# Carte_Oeil.net
KiCad netlist of a schematic drawn in Altium Designer
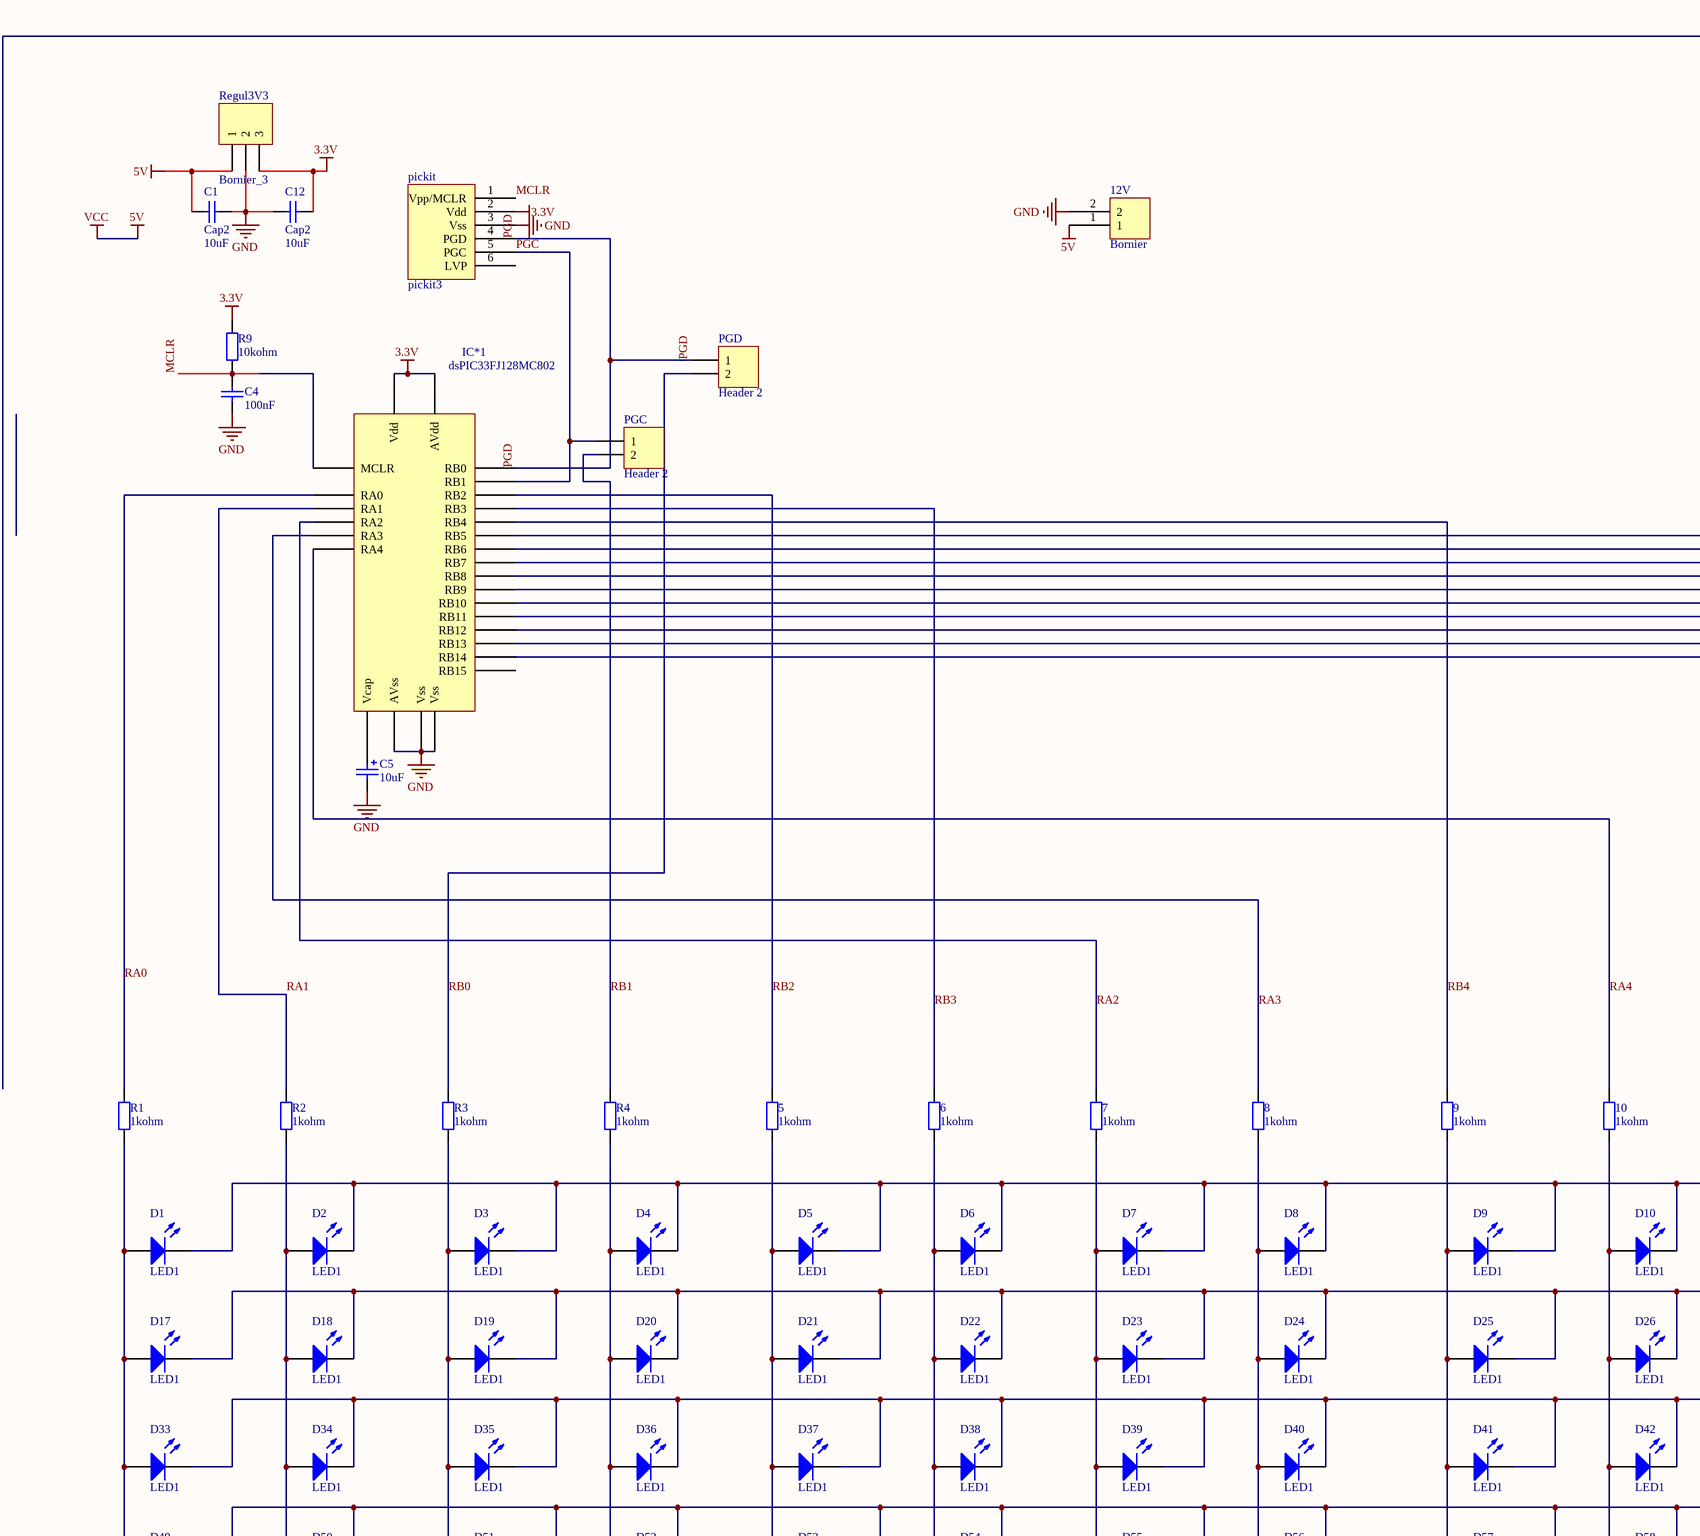
[diagram p0: Carte Oeil.SchDoc, top left]
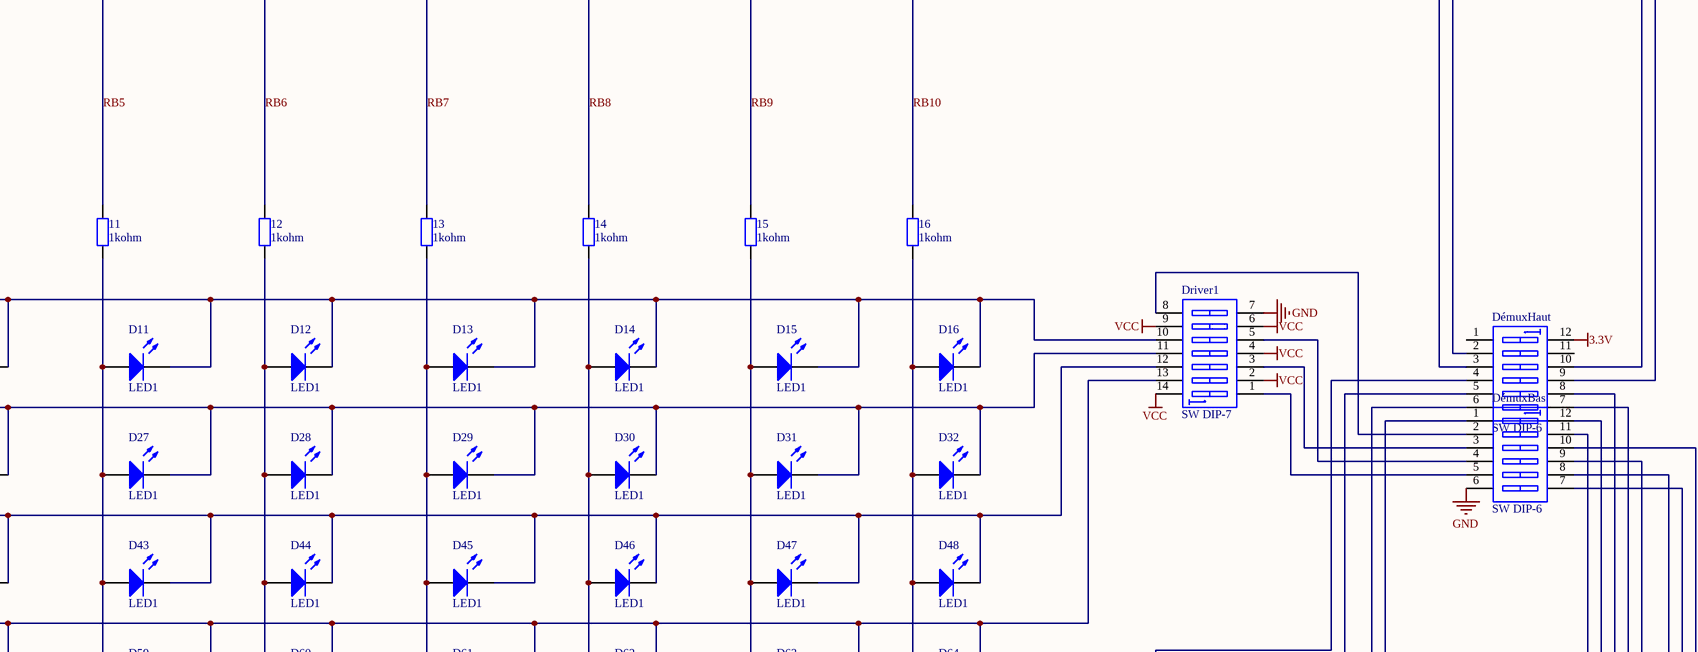
[diagram p1: Carte Oeil.SchDoc, top right]
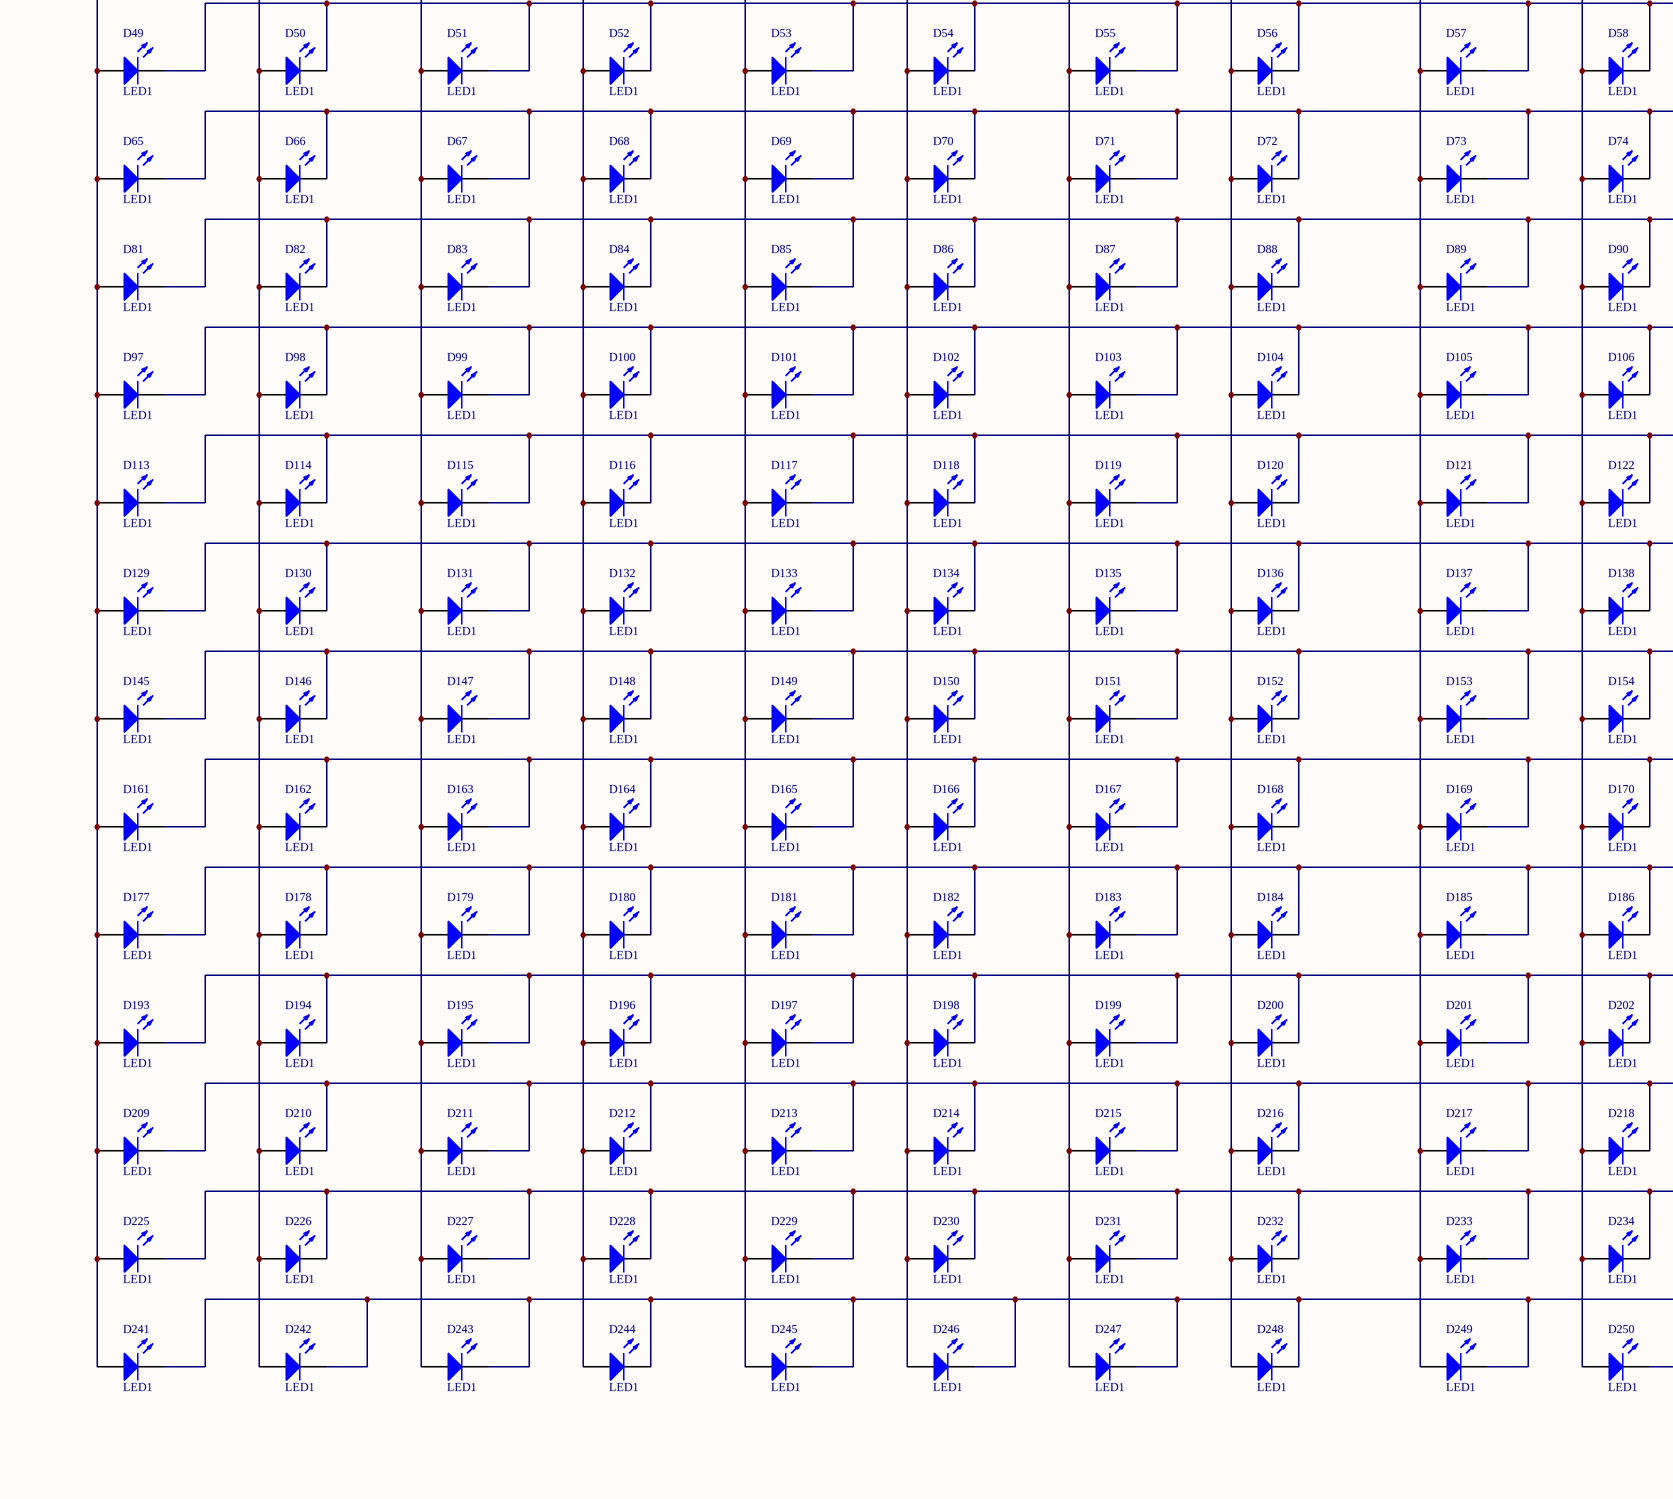
[diagram p2: Carte Oeil.SchDoc, bottom left]
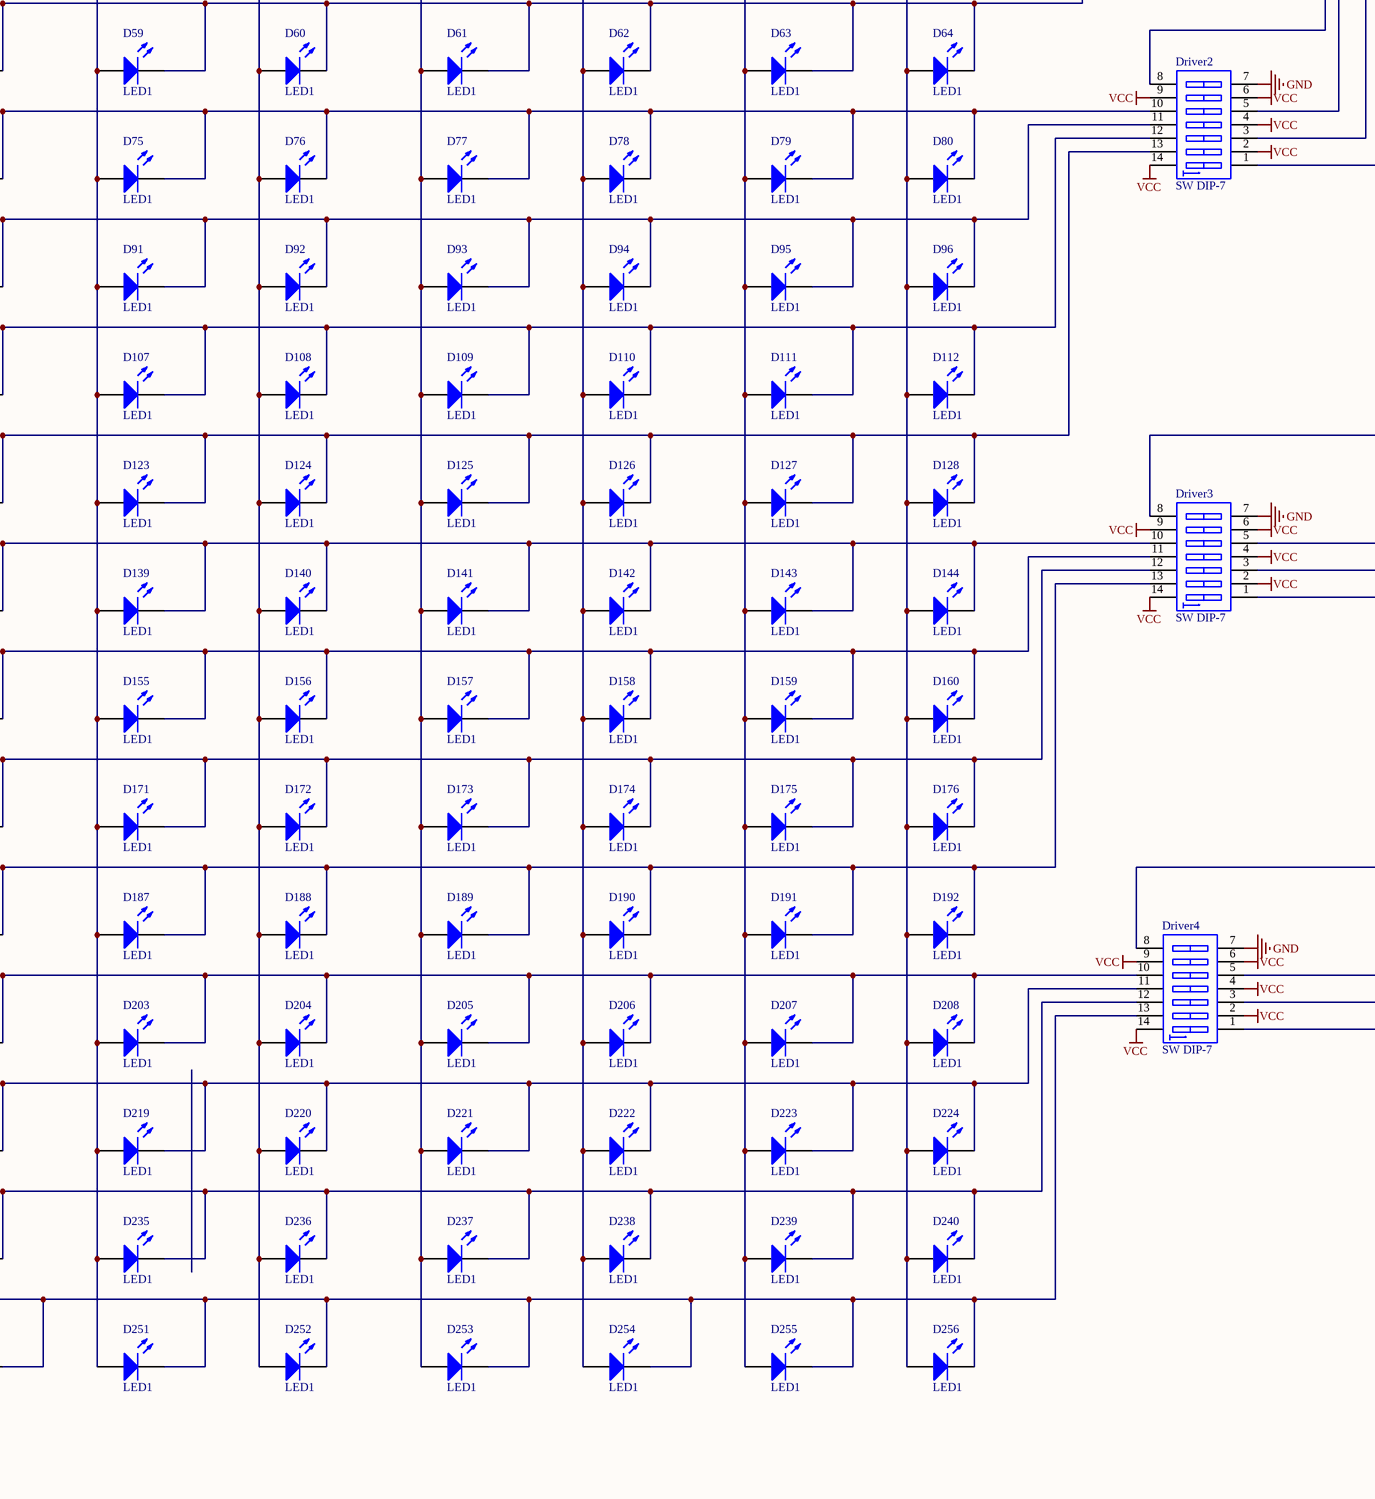
[diagram p3: Carte Oeil.SchDoc, bottom right]

(export (version "E")
  (design (tool "Eeschema 10.0.6"))
  (components
    (comp (ref "5")
      (value "1kohm")
      (footprint "AXIAL-0.5")
      (libsource (lib "lib_robotronik26092013") (part "Resistance"))
    )
    (comp (ref "6")
      (value "1kohm")
      (footprint "AXIAL-0.5")
      (libsource (lib "lib_robotronik26092013") (part "Resistance"))
    )
    (comp (ref "7")
      (value "1kohm")
      (footprint "AXIAL-0.5")
      (libsource (lib "lib_robotronik26092013") (part "Resistance"))
    )
    (comp (ref "8")
      (value "1kohm")
      (footprint "AXIAL-0.5")
      (libsource (lib "lib_robotronik26092013") (part "Resistance"))
    )
    (comp (ref "9")
      (value "1kohm")
      (footprint "AXIAL-0.5")
      (libsource (lib "lib_robotronik26092013") (part "Resistance"))
    )
    (comp (ref "10")
      (value "1kohm")
      (footprint "AXIAL-0.5")
      (libsource (lib "lib_robotronik26092013") (part "Resistance"))
    )
    (comp (ref "11")
      (value "1kohm")
      (footprint "AXIAL-0.5")
      (libsource (lib "lib_robotronik26092013") (part "Resistance"))
    )
    (comp (ref "12")
      (value "1kohm")
      (footprint "AXIAL-0.5")
      (libsource (lib "lib_robotronik26092013") (part "Resistance"))
    )
    (comp (ref "12V")
      (value "Bornier")
      (footprint "Bornier")
      (libsource (lib "lib_Robotronik") (part "Bornier2"))
    )
    (comp (ref "13")
      (value "1kohm")
      (footprint "AXIAL-0.5")
      (libsource (lib "lib_robotronik26092013") (part "Resistance"))
    )
    (comp (ref "14")
      (value "1kohm")
      (footprint "AXIAL-0.5")
      (libsource (lib "lib_robotronik26092013") (part "Resistance"))
    )
    (comp (ref "15")
      (value "1kohm")
      (footprint "AXIAL-0.5")
      (libsource (lib "lib_robotronik26092013") (part "Resistance"))
    )
    (comp (ref "16")
      (value "1kohm")
      (footprint "AXIAL-0.5")
      (libsource (lib "lib_robotronik26092013") (part "Resistance"))
    )
    (comp (ref "C1")
      (value "Cap2")
      (footprint "AXIAL-0.5")
      (description "Capacitor")
      (fields (field (name "ALTIUM_VALUE") "10uF") (field (name "PUBLISHER") "Altium Limited"))
      (libsource (lib "LIBRAIRIE_INTEGREE_PHELMA1") (part "Cap2"))
    )
    (comp (ref "C4") (value "100nF") (footprint "AXIAL-0.5") (libsource (lib "lib_Robotronik") (part "Capa")))
    (comp (ref "C5")
      (value "10uF")
      (footprint "AXIAL-0.5")
      (libsource (lib "lib_Robotronik") (part "Capa Pol"))
    )
    (comp (ref "C12")
      (value "Cap2")
      (footprint "AXIAL-0.5")
      (description "Capacitor")
      (fields (field (name "ALTIUM_VALUE") "10uF") (field (name "PUBLISHER") "Altium Limited"))
      (libsource (lib "LIBRAIRIE_INTEGREE_PHELMA1") (part "Cap2"))
    )
    (comp (ref "D1")
      (value "LED1")
      (footprint "LED-1")
      (description "Typical RED GaAs LED")
      (fields (field (name "PUBLISHER") "Altium Limited"))
      (libsource (lib "Miscellaneous Devices") (part "LED1"))
    )
    (comp (ref "D2")
      (value "LED1")
      (footprint "LED-1")
      (description "Typical RED GaAs LED")
      (fields (field (name "PUBLISHER") "Altium Limited"))
      (libsource (lib "Miscellaneous Devices") (part "LED1"))
    )
    (comp (ref "D3")
      (value "LED1")
      (footprint "LED-1")
      (description "Typical RED GaAs LED")
      (fields (field (name "PUBLISHER") "Altium Limited"))
      (libsource (lib "Miscellaneous Devices") (part "LED1"))
    )
    (comp (ref "D4")
      (value "LED1")
      (footprint "LED-1")
      (description "Typical RED GaAs LED")
      (fields (field (name "PUBLISHER") "Altium Limited"))
      (libsource (lib "Miscellaneous Devices") (part "LED1"))
    )
    (comp (ref "D5")
      (value "LED1")
      (footprint "LED-1")
      (description "Typical RED GaAs LED")
      (fields (field (name "PUBLISHER") "Altium Limited"))
      (libsource (lib "Miscellaneous Devices") (part "LED1"))
    )
    (comp (ref "D6")
      (value "LED1")
      (footprint "LED-1")
      (description "Typical RED GaAs LED")
      (fields (field (name "PUBLISHER") "Altium Limited"))
      (libsource (lib "Miscellaneous Devices") (part "LED1"))
    )
    (comp (ref "D7")
      (value "LED1")
      (footprint "LED-1")
      (description "Typical RED GaAs LED")
      (fields (field (name "PUBLISHER") "Altium Limited"))
      (libsource (lib "Miscellaneous Devices") (part "LED1"))
    )
    (comp (ref "D8")
      (value "LED1")
      (footprint "LED-1")
      (description "Typical RED GaAs LED")
      (fields (field (name "PUBLISHER") "Altium Limited"))
      (libsource (lib "Miscellaneous Devices") (part "LED1"))
    )
    (comp (ref "D9")
      (value "LED1")
      (footprint "LED-1")
      (description "Typical RED GaAs LED")
      (fields (field (name "PUBLISHER") "Altium Limited"))
      (libsource (lib "Miscellaneous Devices") (part "LED1"))
    )
    (comp (ref "D10")
      (value "LED1")
      (footprint "LED-1")
      (description "Typical RED GaAs LED")
      (fields (field (name "PUBLISHER") "Altium Limited"))
      (libsource (lib "Miscellaneous Devices") (part "LED1"))
    )
    (comp (ref "D11")
      (value "LED1")
      (footprint "LED-1")
      (description "Typical RED GaAs LED")
      (fields (field (name "PUBLISHER") "Altium Limited"))
      (libsource (lib "Miscellaneous Devices") (part "LED1"))
    )
    (comp (ref "D12")
      (value "LED1")
      (footprint "LED-1")
      (description "Typical RED GaAs LED")
      (fields (field (name "PUBLISHER") "Altium Limited"))
      (libsource (lib "Miscellaneous Devices") (part "LED1"))
    )
    (comp (ref "D13")
      (value "LED1")
      (footprint "LED-1")
      (description "Typical RED GaAs LED")
      (fields (field (name "PUBLISHER") "Altium Limited"))
      (libsource (lib "Miscellaneous Devices") (part "LED1"))
    )
    (comp (ref "D14")
      (value "LED1")
      (footprint "LED-1")
      (description "Typical RED GaAs LED")
      (fields (field (name "PUBLISHER") "Altium Limited"))
      (libsource (lib "Miscellaneous Devices") (part "LED1"))
    )
    (comp (ref "D15")
      (value "LED1")
      (footprint "LED-1")
      (description "Typical RED GaAs LED")
      (fields (field (name "PUBLISHER") "Altium Limited"))
      (libsource (lib "Miscellaneous Devices") (part "LED1"))
    )
    (comp (ref "D16")
      (value "LED1")
      (footprint "LED-1")
      (description "Typical RED GaAs LED")
      (fields (field (name "PUBLISHER") "Altium Limited"))
      (libsource (lib "Miscellaneous Devices") (part "LED1"))
    )
    (comp (ref "D17")
      (value "LED1")
      (footprint "LED-1")
      (description "Typical RED GaAs LED")
      (fields (field (name "PUBLISHER") "Altium Limited"))
      (libsource (lib "Miscellaneous Devices") (part "LED1"))
    )
    (comp (ref "D18")
      (value "LED1")
      (footprint "LED-1")
      (description "Typical RED GaAs LED")
      (fields (field (name "PUBLISHER") "Altium Limited"))
      (libsource (lib "Miscellaneous Devices") (part "LED1"))
    )
    (comp (ref "D19")
      (value "LED1")
      (footprint "LED-1")
      (description "Typical RED GaAs LED")
      (fields (field (name "PUBLISHER") "Altium Limited"))
      (libsource (lib "Miscellaneous Devices") (part "LED1"))
    )
    (comp (ref "D20")
      (value "LED1")
      (footprint "LED-1")
      (description "Typical RED GaAs LED")
      (fields (field (name "PUBLISHER") "Altium Limited"))
      (libsource (lib "Miscellaneous Devices") (part "LED1"))
    )
    (comp (ref "D21")
      (value "LED1")
      (footprint "LED-1")
      (description "Typical RED GaAs LED")
      (fields (field (name "PUBLISHER") "Altium Limited"))
      (libsource (lib "Miscellaneous Devices") (part "LED1"))
    )
    (comp (ref "D22")
      (value "LED1")
      (footprint "LED-1")
      (description "Typical RED GaAs LED")
      (fields (field (name "PUBLISHER") "Altium Limited"))
      (libsource (lib "Miscellaneous Devices") (part "LED1"))
    )
    (comp (ref "D23")
      (value "LED1")
      (footprint "LED-1")
      (description "Typical RED GaAs LED")
      (fields (field (name "PUBLISHER") "Altium Limited"))
      (libsource (lib "Miscellaneous Devices") (part "LED1"))
    )
    (comp (ref "D24")
      (value "LED1")
      (footprint "LED-1")
      (description "Typical RED GaAs LED")
      (fields (field (name "PUBLISHER") "Altium Limited"))
      (libsource (lib "Miscellaneous Devices") (part "LED1"))
    )
    (comp (ref "D25")
      (value "LED1")
      (footprint "LED-1")
      (description "Typical RED GaAs LED")
      (fields (field (name "PUBLISHER") "Altium Limited"))
      (libsource (lib "Miscellaneous Devices") (part "LED1"))
    )
    (comp (ref "D26")
      (value "LED1")
      (footprint "LED-1")
      (description "Typical RED GaAs LED")
      (fields (field (name "PUBLISHER") "Altium Limited"))
      (libsource (lib "Miscellaneous Devices") (part "LED1"))
    )
    (comp (ref "D27")
      (value "LED1")
      (footprint "LED-1")
      (description "Typical RED GaAs LED")
      (fields (field (name "PUBLISHER") "Altium Limited"))
      (libsource (lib "Miscellaneous Devices") (part "LED1"))
    )
    (comp (ref "D28")
      (value "LED1")
      (footprint "LED-1")
      (description "Typical RED GaAs LED")
      (fields (field (name "PUBLISHER") "Altium Limited"))
      (libsource (lib "Miscellaneous Devices") (part "LED1"))
    )
    (comp (ref "D29")
      (value "LED1")
      (footprint "LED-1")
      (description "Typical RED GaAs LED")
      (fields (field (name "PUBLISHER") "Altium Limited"))
      (libsource (lib "Miscellaneous Devices") (part "LED1"))
    )
    (comp (ref "D30")
      (value "LED1")
      (footprint "LED-1")
      (description "Typical RED GaAs LED")
      (fields (field (name "PUBLISHER") "Altium Limited"))
      (libsource (lib "Miscellaneous Devices") (part "LED1"))
    )
    (comp (ref "D31")
      (value "LED1")
      (footprint "LED-1")
      (description "Typical RED GaAs LED")
      (fields (field (name "PUBLISHER") "Altium Limited"))
      (libsource (lib "Miscellaneous Devices") (part "LED1"))
    )
    (comp (ref "D32")
      (value "LED1")
      (footprint "LED-1")
      (description "Typical RED GaAs LED")
      (fields (field (name "PUBLISHER") "Altium Limited"))
      (libsource (lib "Miscellaneous Devices") (part "LED1"))
    )
    (comp (ref "D33")
      (value "LED1")
      (footprint "LED-1")
      (description "Typical RED GaAs LED")
      (fields (field (name "PUBLISHER") "Altium Limited"))
      (libsource (lib "Miscellaneous Devices") (part "LED1"))
    )
    (comp (ref "D34")
      (value "LED1")
      (footprint "LED-1")
      (description "Typical RED GaAs LED")
      (fields (field (name "PUBLISHER") "Altium Limited"))
      (libsource (lib "Miscellaneous Devices") (part "LED1"))
    )
    (comp (ref "D35")
      (value "LED1")
      (footprint "LED-1")
      (description "Typical RED GaAs LED")
      (fields (field (name "PUBLISHER") "Altium Limited"))
      (libsource (lib "Miscellaneous Devices") (part "LED1"))
    )
    (comp (ref "D36")
      (value "LED1")
      (footprint "LED-1")
      (description "Typical RED GaAs LED")
      (fields (field (name "PUBLISHER") "Altium Limited"))
      (libsource (lib "Miscellaneous Devices") (part "LED1"))
    )
    (comp (ref "D37")
      (value "LED1")
      (footprint "LED-1")
      (description "Typical RED GaAs LED")
      (fields (field (name "PUBLISHER") "Altium Limited"))
      (libsource (lib "Miscellaneous Devices") (part "LED1"))
    )
    (comp (ref "D38")
      (value "LED1")
      (footprint "LED-1")
      (description "Typical RED GaAs LED")
      (fields (field (name "PUBLISHER") "Altium Limited"))
      (libsource (lib "Miscellaneous Devices") (part "LED1"))
    )
    (comp (ref "D39")
      (value "LED1")
      (footprint "LED-1")
      (description "Typical RED GaAs LED")
      (fields (field (name "PUBLISHER") "Altium Limited"))
      (libsource (lib "Miscellaneous Devices") (part "LED1"))
    )
    (comp (ref "D40")
      (value "LED1")
      (footprint "LED-1")
      (description "Typical RED GaAs LED")
      (fields (field (name "PUBLISHER") "Altium Limited"))
      (libsource (lib "Miscellaneous Devices") (part "LED1"))
    )
    (comp (ref "D41")
      (value "LED1")
      (footprint "LED-1")
      (description "Typical RED GaAs LED")
      (fields (field (name "PUBLISHER") "Altium Limited"))
      (libsource (lib "Miscellaneous Devices") (part "LED1"))
    )
    (comp (ref "D42")
      (value "LED1")
      (footprint "LED-1")
      (description "Typical RED GaAs LED")
      (fields (field (name "PUBLISHER") "Altium Limited"))
      (libsource (lib "Miscellaneous Devices") (part "LED1"))
    )
    (comp (ref "D43")
      (value "LED1")
      (footprint "LED-1")
      (description "Typical RED GaAs LED")
      (fields (field (name "PUBLISHER") "Altium Limited"))
      (libsource (lib "Miscellaneous Devices") (part "LED1"))
    )
    (comp (ref "D44")
      (value "LED1")
      (footprint "LED-1")
      (description "Typical RED GaAs LED")
      (fields (field (name "PUBLISHER") "Altium Limited"))
      (libsource (lib "Miscellaneous Devices") (part "LED1"))
    )
    (comp (ref "D45")
      (value "LED1")
      (footprint "LED-1")
      (description "Typical RED GaAs LED")
      (fields (field (name "PUBLISHER") "Altium Limited"))
      (libsource (lib "Miscellaneous Devices") (part "LED1"))
    )
    (comp (ref "D46")
      (value "LED1")
      (footprint "LED-1")
      (description "Typical RED GaAs LED")
      (fields (field (name "PUBLISHER") "Altium Limited"))
      (libsource (lib "Miscellaneous Devices") (part "LED1"))
    )
    (comp (ref "D47")
      (value "LED1")
      (footprint "LED-1")
      (description "Typical RED GaAs LED")
      (fields (field (name "PUBLISHER") "Altium Limited"))
      (libsource (lib "Miscellaneous Devices") (part "LED1"))
    )
    (comp (ref "D48")
      (value "LED1")
      (footprint "LED-1")
      (description "Typical RED GaAs LED")
      (fields (field (name "PUBLISHER") "Altium Limited"))
      (libsource (lib "Miscellaneous Devices") (part "LED1"))
    )
    (comp (ref "D49")
      (value "LED1")
      (footprint "LED-1")
      (description "Typical RED GaAs LED")
      (fields (field (name "PUBLISHER") "Altium Limited"))
      (libsource (lib "Miscellaneous Devices") (part "LED1"))
    )
    (comp (ref "D50")
      (value "LED1")
      (footprint "LED-1")
      (description "Typical RED GaAs LED")
      (fields (field (name "PUBLISHER") "Altium Limited"))
      (libsource (lib "Miscellaneous Devices") (part "LED1"))
    )
    (comp (ref "D51")
      (value "LED1")
      (footprint "LED-1")
      (description "Typical RED GaAs LED")
      (fields (field (name "PUBLISHER") "Altium Limited"))
      (libsource (lib "Miscellaneous Devices") (part "LED1"))
    )
    (comp (ref "D52")
      (value "LED1")
      (footprint "LED-1")
      (description "Typical RED GaAs LED")
      (fields (field (name "PUBLISHER") "Altium Limited"))
      (libsource (lib "Miscellaneous Devices") (part "LED1"))
    )
    (comp (ref "D53")
      (value "LED1")
      (footprint "LED-1")
      (description "Typical RED GaAs LED")
      (fields (field (name "PUBLISHER") "Altium Limited"))
      (libsource (lib "Miscellaneous Devices") (part "LED1"))
    )
    (comp (ref "D54")
      (value "LED1")
      (footprint "LED-1")
      (description "Typical RED GaAs LED")
      (fields (field (name "PUBLISHER") "Altium Limited"))
      (libsource (lib "Miscellaneous Devices") (part "LED1"))
    )
    (comp (ref "D55")
      (value "LED1")
      (footprint "LED-1")
      (description "Typical RED GaAs LED")
      (fields (field (name "PUBLISHER") "Altium Limited"))
      (libsource (lib "Miscellaneous Devices") (part "LED1"))
    )
    (comp (ref "D56")
      (value "LED1")
      (footprint "LED-1")
      (description "Typical RED GaAs LED")
      (fields (field (name "PUBLISHER") "Altium Limited"))
      (libsource (lib "Miscellaneous Devices") (part "LED1"))
    )
    (comp (ref "D57")
      (value "LED1")
      (footprint "LED-1")
      (description "Typical RED GaAs LED")
      (fields (field (name "PUBLISHER") "Altium Limited"))
      (libsource (lib "Miscellaneous Devices") (part "LED1"))
    )
    (comp (ref "D58")
      (value "LED1")
      (footprint "LED-1")
      (description "Typical RED GaAs LED")
      (fields (field (name "PUBLISHER") "Altium Limited"))
      (libsource (lib "Miscellaneous Devices") (part "LED1"))
    )
    (comp (ref "D59")
      (value "LED1")
      (footprint "LED-1")
      (description "Typical RED GaAs LED")
      (fields (field (name "PUBLISHER") "Altium Limited"))
      (libsource (lib "Miscellaneous Devices") (part "LED1"))
    )
    (comp (ref "D60")
      (value "LED1")
      (footprint "LED-1")
      (description "Typical RED GaAs LED")
      (fields (field (name "PUBLISHER") "Altium Limited"))
      (libsource (lib "Miscellaneous Devices") (part "LED1"))
    )
    (comp (ref "D61")
      (value "LED1")
      (footprint "LED-1")
      (description "Typical RED GaAs LED")
      (fields (field (name "PUBLISHER") "Altium Limited"))
      (libsource (lib "Miscellaneous Devices") (part "LED1"))
    )
    (comp (ref "D62")
      (value "LED1")
      (footprint "LED-1")
      (description "Typical RED GaAs LED")
      (fields (field (name "PUBLISHER") "Altium Limited"))
      (libsource (lib "Miscellaneous Devices") (part "LED1"))
    )
    (comp (ref "D63")
      (value "LED1")
      (footprint "LED-1")
      (description "Typical RED GaAs LED")
      (fields (field (name "PUBLISHER") "Altium Limited"))
      (libsource (lib "Miscellaneous Devices") (part "LED1"))
    )
    (comp (ref "D64")
      (value "LED1")
      (footprint "LED-1")
      (description "Typical RED GaAs LED")
      (fields (field (name "PUBLISHER") "Altium Limited"))
      (libsource (lib "Miscellaneous Devices") (part "LED1"))
    )
    (comp (ref "D65")
      (value "LED1")
      (footprint "LED-1")
      (description "Typical RED GaAs LED")
      (fields (field (name "PUBLISHER") "Altium Limited"))
      (libsource (lib "Miscellaneous Devices") (part "LED1"))
    )
    (comp (ref "D66")
      (value "LED1")
      (footprint "LED-1")
      (description "Typical RED GaAs LED")
      (fields (field (name "PUBLISHER") "Altium Limited"))
      (libsource (lib "Miscellaneous Devices") (part "LED1"))
    )
    (comp (ref "D67")
      (value "LED1")
      (footprint "LED-1")
      (description "Typical RED GaAs LED")
      (fields (field (name "PUBLISHER") "Altium Limited"))
      (libsource (lib "Miscellaneous Devices") (part "LED1"))
    )
    (comp (ref "D68")
      (value "LED1")
      (footprint "LED-1")
      (description "Typical RED GaAs LED")
      (fields (field (name "PUBLISHER") "Altium Limited"))
      (libsource (lib "Miscellaneous Devices") (part "LED1"))
    )
    (comp (ref "D69")
      (value "LED1")
      (footprint "LED-1")
      (description "Typical RED GaAs LED")
      (fields (field (name "PUBLISHER") "Altium Limited"))
      (libsource (lib "Miscellaneous Devices") (part "LED1"))
    )
    (comp (ref "D70")
      (value "LED1")
      (footprint "LED-1")
      (description "Typical RED GaAs LED")
      (fields (field (name "PUBLISHER") "Altium Limited"))
      (libsource (lib "Miscellaneous Devices") (part "LED1"))
    )
    (comp (ref "D71")
      (value "LED1")
      (footprint "LED-1")
      (description "Typical RED GaAs LED")
      (fields (field (name "PUBLISHER") "Altium Limited"))
      (libsource (lib "Miscellaneous Devices") (part "LED1"))
    )
    (comp (ref "D72")
      (value "LED1")
      (footprint "LED-1")
      (description "Typical RED GaAs LED")
      (fields (field (name "PUBLISHER") "Altium Limited"))
      (libsource (lib "Miscellaneous Devices") (part "LED1"))
    )
    (comp (ref "D73")
      (value "LED1")
      (footprint "LED-1")
      (description "Typical RED GaAs LED")
      (fields (field (name "PUBLISHER") "Altium Limited"))
      (libsource (lib "Miscellaneous Devices") (part "LED1"))
    )
    (comp (ref "D74")
      (value "LED1")
      (footprint "LED-1")
      (description "Typical RED GaAs LED")
      (fields (field (name "PUBLISHER") "Altium Limited"))
      (libsource (lib "Miscellaneous Devices") (part "LED1"))
    )
    (comp (ref "D75")
      (value "LED1")
      (footprint "LED-1")
      (description "Typical RED GaAs LED")
      (fields (field (name "PUBLISHER") "Altium Limited"))
      (libsource (lib "Miscellaneous Devices") (part "LED1"))
    )
    (comp (ref "D76")
      (value "LED1")
      (footprint "LED-1")
      (description "Typical RED GaAs LED")
      (fields (field (name "PUBLISHER") "Altium Limited"))
      (libsource (lib "Miscellaneous Devices") (part "LED1"))
    )
    (comp (ref "D77")
      (value "LED1")
      (footprint "LED-1")
      (description "Typical RED GaAs LED")
      (fields (field (name "PUBLISHER") "Altium Limited"))
      (libsource (lib "Miscellaneous Devices") (part "LED1"))
    )
    (comp (ref "D78")
      (value "LED1")
      (footprint "LED-1")
      (description "Typical RED GaAs LED")
      (fields (field (name "PUBLISHER") "Altium Limited"))
      (libsource (lib "Miscellaneous Devices") (part "LED1"))
    )
    (comp (ref "D79")
      (value "LED1")
      (footprint "LED-1")
      (description "Typical RED GaAs LED")
      (fields (field (name "PUBLISHER") "Altium Limited"))
      (libsource (lib "Miscellaneous Devices") (part "LED1"))
    )
    (comp (ref "D80")
      (value "LED1")
      (footprint "LED-1")
      (description "Typical RED GaAs LED")
      (fields (field (name "PUBLISHER") "Altium Limited"))
      (libsource (lib "Miscellaneous Devices") (part "LED1"))
    )
    (comp (ref "D81")
      (value "LED1")
      (footprint "LED-1")
      (description "Typical RED GaAs LED")
      (fields (field (name "PUBLISHER") "Altium Limited"))
      (libsource (lib "Miscellaneous Devices") (part "LED1"))
    )
    (comp (ref "D82")
      (value "LED1")
      (footprint "LED-1")
      (description "Typical RED GaAs LED")
      (fields (field (name "PUBLISHER") "Altium Limited"))
      (libsource (lib "Miscellaneous Devices") (part "LED1"))
    )
    (comp (ref "D83")
      (value "LED1")
      (footprint "LED-1")
      (description "Typical RED GaAs LED")
      (fields (field (name "PUBLISHER") "Altium Limited"))
      (libsource (lib "Miscellaneous Devices") (part "LED1"))
    )
    (comp (ref "D84")
      (value "LED1")
      (footprint "LED-1")
      (description "Typical RED GaAs LED")
      (fields (field (name "PUBLISHER") "Altium Limited"))
      (libsource (lib "Miscellaneous Devices") (part "LED1"))
    )
    (comp (ref "D85")
      (value "LED1")
      (footprint "LED-1")
      (description "Typical RED GaAs LED")
      (fields (field (name "PUBLISHER") "Altium Limited"))
      (libsource (lib "Miscellaneous Devices") (part "LED1"))
    )
    (comp (ref "D86")
      (value "LED1")
      (footprint "LED-1")
      (description "Typical RED GaAs LED")
      (fields (field (name "PUBLISHER") "Altium Limited"))
      (libsource (lib "Miscellaneous Devices") (part "LED1"))
    )
    (comp (ref "D87")
      (value "LED1")
      (footprint "LED-1")
      (description "Typical RED GaAs LED")
      (fields (field (name "PUBLISHER") "Altium Limited"))
      (libsource (lib "Miscellaneous Devices") (part "LED1"))
    )
    (comp (ref "D88")
      (value "LED1")
      (footprint "LED-1")
      (description "Typical RED GaAs LED")
      (fields (field (name "PUBLISHER") "Altium Limited"))
      (libsource (lib "Miscellaneous Devices") (part "LED1"))
    )
    (comp (ref "D89")
      (value "LED1")
      (footprint "LED-1")
      (description "Typical RED GaAs LED")
      (fields (field (name "PUBLISHER") "Altium Limited"))
      (libsource (lib "Miscellaneous Devices") (part "LED1"))
    )
    (comp (ref "D90")
      (value "LED1")
      (footprint "LED-1")
      (description "Typical RED GaAs LED")
      (fields (field (name "PUBLISHER") "Altium Limited"))
      (libsource (lib "Miscellaneous Devices") (part "LED1"))
    )
    (comp (ref "D91")
      (value "LED1")
      (footprint "LED-1")
      (description "Typical RED GaAs LED")
      (fields (field (name "PUBLISHER") "Altium Limited"))
      (libsource (lib "Miscellaneous Devices") (part "LED1"))
    )
    (comp (ref "D92")
      (value "LED1")
      (footprint "LED-1")
      (description "Typical RED GaAs LED")
      (fields (field (name "PUBLISHER") "Altium Limited"))
      (libsource (lib "Miscellaneous Devices") (part "LED1"))
    )
    (comp (ref "D93")
      (value "LED1")
      (footprint "LED-1")
      (description "Typical RED GaAs LED")
      (fields (field (name "PUBLISHER") "Altium Limited"))
      (libsource (lib "Miscellaneous Devices") (part "LED1"))
    )
    (comp (ref "D94")
      (value "LED1")
      (footprint "LED-1")
      (description "Typical RED GaAs LED")
      (fields (field (name "PUBLISHER") "Altium Limited"))
      (libsource (lib "Miscellaneous Devices") (part "LED1"))
    )
    (comp (ref "D95")
      (value "LED1")
      (footprint "LED-1")
      (description "Typical RED GaAs LED")
      (fields (field (name "PUBLISHER") "Altium Limited"))
      (libsource (lib "Miscellaneous Devices") (part "LED1"))
    )
    (comp (ref "D96")
      (value "LED1")
      (footprint "LED-1")
      (description "Typical RED GaAs LED")
      (fields (field (name "PUBLISHER") "Altium Limited"))
      (libsource (lib "Miscellaneous Devices") (part "LED1"))
    )
    (comp (ref "D97")
      (value "LED1")
      (footprint "LED-1")
      (description "Typical RED GaAs LED")
      (fields (field (name "PUBLISHER") "Altium Limited"))
      (libsource (lib "Miscellaneous Devices") (part "LED1"))
    )
    (comp (ref "D98")
      (value "LED1")
      (footprint "LED-1")
      (description "Typical RED GaAs LED")
      (fields (field (name "PUBLISHER") "Altium Limited"))
      (libsource (lib "Miscellaneous Devices") (part "LED1"))
    )
    (comp (ref "D99")
      (value "LED1")
      (footprint "LED-1")
      (description "Typical RED GaAs LED")
      (fields (field (name "PUBLISHER") "Altium Limited"))
      (libsource (lib "Miscellaneous Devices") (part "LED1"))
    )
    (comp (ref "D100")
      (value "LED1")
      (footprint "LED-1")
      (description "Typical RED GaAs LED")
      (fields (field (name "PUBLISHER") "Altium Limited"))
      (libsource (lib "Miscellaneous Devices") (part "LED1"))
    )
    (comp (ref "D101")
      (value "LED1")
      (footprint "LED-1")
      (description "Typical RED GaAs LED")
      (fields (field (name "PUBLISHER") "Altium Limited"))
      (libsource (lib "Miscellaneous Devices") (part "LED1"))
    )
    (comp (ref "D102")
      (value "LED1")
      (footprint "LED-1")
      (description "Typical RED GaAs LED")
      (fields (field (name "PUBLISHER") "Altium Limited"))
      (libsource (lib "Miscellaneous Devices") (part "LED1"))
    )
    (comp (ref "D103")
      (value "LED1")
      (footprint "LED-1")
      (description "Typical RED GaAs LED")
      (fields (field (name "PUBLISHER") "Altium Limited"))
      (libsource (lib "Miscellaneous Devices") (part "LED1"))
    )
    (comp (ref "D104")
      (value "LED1")
      (footprint "LED-1")
      (description "Typical RED GaAs LED")
      (fields (field (name "PUBLISHER") "Altium Limited"))
      (libsource (lib "Miscellaneous Devices") (part "LED1"))
    )
    (comp (ref "D105")
      (value "LED1")
      (footprint "LED-1")
      (description "Typical RED GaAs LED")
      (fields (field (name "PUBLISHER") "Altium Limited"))
      (libsource (lib "Miscellaneous Devices") (part "LED1"))
    )
    (comp (ref "D106")
      (value "LED1")
      (footprint "LED-1")
      (description "Typical RED GaAs LED")
      (fields (field (name "PUBLISHER") "Altium Limited"))
      (libsource (lib "Miscellaneous Devices") (part "LED1"))
    )
    (comp (ref "D107")
      (value "LED1")
      (footprint "LED-1")
      (description "Typical RED GaAs LED")
      (fields (field (name "PUBLISHER") "Altium Limited"))
      (libsource (lib "Miscellaneous Devices") (part "LED1"))
    )
    (comp (ref "D108")
      (value "LED1")
      (footprint "LED-1")
      (description "Typical RED GaAs LED")
      (fields (field (name "PUBLISHER") "Altium Limited"))
      (libsource (lib "Miscellaneous Devices") (part "LED1"))
    )
    (comp (ref "D109")
      (value "LED1")
      (footprint "LED-1")
      (description "Typical RED GaAs LED")
      (fields (field (name "PUBLISHER") "Altium Limited"))
      (libsource (lib "Miscellaneous Devices") (part "LED1"))
    )
    (comp (ref "D110")
      (value "LED1")
      (footprint "LED-1")
      (description "Typical RED GaAs LED")
      (fields (field (name "PUBLISHER") "Altium Limited"))
      (libsource (lib "Miscellaneous Devices") (part "LED1"))
    )
    (comp (ref "D111")
      (value "LED1")
      (footprint "LED-1")
      (description "Typical RED GaAs LED")
      (fields (field (name "PUBLISHER") "Altium Limited"))
      (libsource (lib "Miscellaneous Devices") (part "LED1"))
    )
    (comp (ref "D112")
      (value "LED1")
      (footprint "LED-1")
      (description "Typical RED GaAs LED")
      (fields (field (name "PUBLISHER") "Altium Limited"))
      (libsource (lib "Miscellaneous Devices") (part "LED1"))
    )
    (comp (ref "D113")
      (value "LED1")
      (footprint "LED-1")
      (description "Typical RED GaAs LED")
      (fields (field (name "PUBLISHER") "Altium Limited"))
      (libsource (lib "Miscellaneous Devices") (part "LED1"))
    )
    (comp (ref "D114")
      (value "LED1")
      (footprint "LED-1")
      (description "Typical RED GaAs LED")
      (fields (field (name "PUBLISHER") "Altium Limited"))
      (libsource (lib "Miscellaneous Devices") (part "LED1"))
    )
    (comp (ref "D115")
      (value "LED1")
      (footprint "LED-1")
      (description "Typical RED GaAs LED")
      (fields (field (name "PUBLISHER") "Altium Limited"))
      (libsource (lib "Miscellaneous Devices") (part "LED1"))
    )
    (comp (ref "D116")
      (value "LED1")
      (footprint "LED-1")
      (description "Typical RED GaAs LED")
      (fields (field (name "PUBLISHER") "Altium Limited"))
      (libsource (lib "Miscellaneous Devices") (part "LED1"))
    )
    (comp (ref "D117")
      (value "LED1")
      (footprint "LED-1")
      (description "Typical RED GaAs LED")
      (fields (field (name "PUBLISHER") "Altium Limited"))
      (libsource (lib "Miscellaneous Devices") (part "LED1"))
    )
    (comp (ref "D118")
      (value "LED1")
      (footprint "LED-1")
      (description "Typical RED GaAs LED")
      (fields (field (name "PUBLISHER") "Altium Limited"))
      (libsource (lib "Miscellaneous Devices") (part "LED1"))
    )
    (comp (ref "D119")
      (value "LED1")
      (footprint "LED-1")
      (description "Typical RED GaAs LED")
      (fields (field (name "PUBLISHER") "Altium Limited"))
      (libsource (lib "Miscellaneous Devices") (part "LED1"))
    )
    (comp (ref "D120")
      (value "LED1")
      (footprint "LED-1")
      (description "Typical RED GaAs LED")
      (fields (field (name "PUBLISHER") "Altium Limited"))
      (libsource (lib "Miscellaneous Devices") (part "LED1"))
    )
    (comp (ref "D121")
      (value "LED1")
      (footprint "LED-1")
      (description "Typical RED GaAs LED")
      (fields (field (name "PUBLISHER") "Altium Limited"))
      (libsource (lib "Miscellaneous Devices") (part "LED1"))
    )
    (comp (ref "D122")
      (value "LED1")
      (footprint "LED-1")
      (description "Typical RED GaAs LED")
      (fields (field (name "PUBLISHER") "Altium Limited"))
      (libsource (lib "Miscellaneous Devices") (part "LED1"))
    )
    (comp (ref "D123")
      (value "LED1")
      (footprint "LED-1")
      (description "Typical RED GaAs LED")
      (fields (field (name "PUBLISHER") "Altium Limited"))
      (libsource (lib "Miscellaneous Devices") (part "LED1"))
    )
    (comp (ref "D124")
      (value "LED1")
      (footprint "LED-1")
      (description "Typical RED GaAs LED")
      (fields (field (name "PUBLISHER") "Altium Limited"))
      (libsource (lib "Miscellaneous Devices") (part "LED1"))
    )
    (comp (ref "D125")
      (value "LED1")
      (footprint "LED-1")
      (description "Typical RED GaAs LED")
      (fields (field (name "PUBLISHER") "Altium Limited"))
      (libsource (lib "Miscellaneous Devices") (part "LED1"))
    )
    (comp (ref "D126")
      (value "LED1")
      (footprint "LED-1")
      (description "Typical RED GaAs LED")
      (fields (field (name "PUBLISHER") "Altium Limited"))
      (libsource (lib "Miscellaneous Devices") (part "LED1"))
    )
    (comp (ref "D127")
      (value "LED1")
      (footprint "LED-1")
      (description "Typical RED GaAs LED")
      (fields (field (name "PUBLISHER") "Altium Limited"))
      (libsource (lib "Miscellaneous Devices") (part "LED1"))
    )
    (comp (ref "D128")
      (value "LED1")
      (footprint "LED-1")
      (description "Typical RED GaAs LED")
      (fields (field (name "PUBLISHER") "Altium Limited"))
      (libsource (lib "Miscellaneous Devices") (part "LED1"))
    )
    (comp (ref "D129")
      (value "LED1")
      (footprint "LED-1")
      (description "Typical RED GaAs LED")
      (fields (field (name "PUBLISHER") "Altium Limited"))
      (libsource (lib "Miscellaneous Devices") (part "LED1"))
    )
    (comp (ref "D130")
      (value "LED1")
      (footprint "LED-1")
      (description "Typical RED GaAs LED")
      (fields (field (name "PUBLISHER") "Altium Limited"))
      (libsource (lib "Miscellaneous Devices") (part "LED1"))
    )
    (comp (ref "D131")
      (value "LED1")
      (footprint "LED-1")
      (description "Typical RED GaAs LED")
      (fields (field (name "PUBLISHER") "Altium Limited"))
      (libsource (lib "Miscellaneous Devices") (part "LED1"))
    )
    (comp (ref "D132")
      (value "LED1")
      (footprint "LED-1")
      (description "Typical RED GaAs LED")
      (fields (field (name "PUBLISHER") "Altium Limited"))
      (libsource (lib "Miscellaneous Devices") (part "LED1"))
    )
    (comp (ref "D133")
      (value "LED1")
      (footprint "LED-1")
      (description "Typical RED GaAs LED")
      (fields (field (name "PUBLISHER") "Altium Limited"))
      (libsource (lib "Miscellaneous Devices") (part "LED1"))
    )
    (comp (ref "D134")
      (value "LED1")
      (footprint "LED-1")
      (description "Typical RED GaAs LED")
      (fields (field (name "PUBLISHER") "Altium Limited"))
      (libsource (lib "Miscellaneous Devices") (part "LED1"))
    )
    (comp (ref "D135")
      (value "LED1")
      (footprint "LED-1")
      (description "Typical RED GaAs LED")
      (fields (field (name "PUBLISHER") "Altium Limited"))
      (libsource (lib "Miscellaneous Devices") (part "LED1"))
    )
    (comp (ref "D136")
      (value "LED1")
      (footprint "LED-1")
      (description "Typical RED GaAs LED")
      (fields (field (name "PUBLISHER") "Altium Limited"))
      (libsource (lib "Miscellaneous Devices") (part "LED1"))
    )
    (comp (ref "D137")
      (value "LED1")
      (footprint "LED-1")
      (description "Typical RED GaAs LED")
      (fields (field (name "PUBLISHER") "Altium Limited"))
      (libsource (lib "Miscellaneous Devices") (part "LED1"))
    )
    (comp (ref "D138")
      (value "LED1")
      (footprint "LED-1")
      (description "Typical RED GaAs LED")
      (fields (field (name "PUBLISHER") "Altium Limited"))
      (libsource (lib "Miscellaneous Devices") (part "LED1"))
    )
    (comp (ref "D139")
      (value "LED1")
      (footprint "LED-1")
      (description "Typical RED GaAs LED")
      (fields (field (name "PUBLISHER") "Altium Limited"))
      (libsource (lib "Miscellaneous Devices") (part "LED1"))
    )
    (comp (ref "D140")
      (value "LED1")
      (footprint "LED-1")
      (description "Typical RED GaAs LED")
      (fields (field (name "PUBLISHER") "Altium Limited"))
      (libsource (lib "Miscellaneous Devices") (part "LED1"))
    )
    (comp (ref "D141")
      (value "LED1")
      (footprint "LED-1")
      (description "Typical RED GaAs LED")
      (fields (field (name "PUBLISHER") "Altium Limited"))
      (libsource (lib "Miscellaneous Devices") (part "LED1"))
    )
    (comp (ref "D142")
      (value "LED1")
      (footprint "LED-1")
      (description "Typical RED GaAs LED")
      (fields (field (name "PUBLISHER") "Altium Limited"))
      (libsource (lib "Miscellaneous Devices") (part "LED1"))
    )
    (comp (ref "D143")
      (value "LED1")
      (footprint "LED-1")
      (description "Typical RED GaAs LED")
      (fields (field (name "PUBLISHER") "Altium Limited"))
      (libsource (lib "Miscellaneous Devices") (part "LED1"))
    )
    (comp (ref "D144")
      (value "LED1")
      (footprint "LED-1")
      (description "Typical RED GaAs LED")
      (fields (field (name "PUBLISHER") "Altium Limited"))
      (libsource (lib "Miscellaneous Devices") (part "LED1"))
    )
    (comp (ref "D145")
      (value "LED1")
      (footprint "LED-1")
      (description "Typical RED GaAs LED")
      (fields (field (name "PUBLISHER") "Altium Limited"))
      (libsource (lib "Miscellaneous Devices") (part "LED1"))
    )
    (comp (ref "D146")
      (value "LED1")
      (footprint "LED-1")
      (description "Typical RED GaAs LED")
      (fields (field (name "PUBLISHER") "Altium Limited"))
      (libsource (lib "Miscellaneous Devices") (part "LED1"))
    )
    (comp (ref "D147")
      (value "LED1")
      (footprint "LED-1")
      (description "Typical RED GaAs LED")
      (fields (field (name "PUBLISHER") "Altium Limited"))
      (libsource (lib "Miscellaneous Devices") (part "LED1"))
    )
    (comp (ref "D148")
      (value "LED1")
      (footprint "LED-1")
      (description "Typical RED GaAs LED")
      (fields (field (name "PUBLISHER") "Altium Limited"))
      (libsource (lib "Miscellaneous Devices") (part "LED1"))
    )
    (comp (ref "D149")
      (value "LED1")
      (footprint "LED-1")
      (description "Typical RED GaAs LED")
      (fields (field (name "PUBLISHER") "Altium Limited"))
      (libsource (lib "Miscellaneous Devices") (part "LED1"))
    )
    (comp (ref "D150")
      (value "LED1")
      (footprint "LED-1")
      (description "Typical RED GaAs LED")
      (fields (field (name "PUBLISHER") "Altium Limited"))
      (libsource (lib "Miscellaneous Devices") (part "LED1"))
    )
    (comp (ref "D151")
      (value "LED1")
      (footprint "LED-1")
      (description "Typical RED GaAs LED")
      (fields (field (name "PUBLISHER") "Altium Limited"))
      (libsource (lib "Miscellaneous Devices") (part "LED1"))
    )
    (comp (ref "D152")
      (value "LED1")
      (footprint "LED-1")
      (description "Typical RED GaAs LED")
      (fields (field (name "PUBLISHER") "Altium Limited"))
      (libsource (lib "Miscellaneous Devices") (part "LED1"))
    )
    (comp (ref "D153")
      (value "LED1")
      (footprint "LED-1")
      (description "Typical RED GaAs LED")
      (fields (field (name "PUBLISHER") "Altium Limited"))
      (libsource (lib "Miscellaneous Devices") (part "LED1"))
    )
    (comp (ref "D154")
      (value "LED1")
      (footprint "LED-1")
      (description "Typical RED GaAs LED")
      (fields (field (name "PUBLISHER") "Altium Limited"))
      (libsource (lib "Miscellaneous Devices") (part "LED1"))
    )
    (comp (ref "D155")
      (value "LED1")
      (footprint "LED-1")
      (description "Typical RED GaAs LED")
      (fields (field (name "PUBLISHER") "Altium Limited"))
      (libsource (lib "Miscellaneous Devices") (part "LED1"))
    )
    (comp (ref "D156")
      (value "LED1")
      (footprint "LED-1")
      (description "Typical RED GaAs LED")
      (fields (field (name "PUBLISHER") "Altium Limited"))
      (libsource (lib "Miscellaneous Devices") (part "LED1"))
    )
    (comp (ref "D157")
      (value "LED1")
      (footprint "LED-1")
      (description "Typical RED GaAs LED")
      (fields (field (name "PUBLISHER") "Altium Limited"))
      (libsource (lib "Miscellaneous Devices") (part "LED1"))
    )
    (comp (ref "D158")
      (value "LED1")
      (footprint "LED-1")
      (description "Typical RED GaAs LED")
      (fields (field (name "PUBLISHER") "Altium Limited"))
      (libsource (lib "Miscellaneous Devices") (part "LED1"))
    )
    (comp (ref "D159")
      (value "LED1")
      (footprint "LED-1")
      (description "Typical RED GaAs LED")
      (fields (field (name "PUBLISHER") "Altium Limited"))
      (libsource (lib "Miscellaneous Devices") (part "LED1"))
    )
    (comp (ref "D160")
      (value "LED1")
      (footprint "LED-1")
      (description "Typical RED GaAs LED")
      (fields (field (name "PUBLISHER") "Altium Limited"))
      (libsource (lib "Miscellaneous Devices") (part "LED1"))
    )
    (comp (ref "D161")
      (value "LED1")
      (footprint "LED-1")
      (description "Typical RED GaAs LED")
      (fields (field (name "PUBLISHER") "Altium Limited"))
      (libsource (lib "Miscellaneous Devices") (part "LED1"))
    )
    (comp (ref "D162")
      (value "LED1")
      (footprint "LED-1")
      (description "Typical RED GaAs LED")
      (fields (field (name "PUBLISHER") "Altium Limited"))
      (libsource (lib "Miscellaneous Devices") (part "LED1"))
    )
    (comp (ref "D163")
      (value "LED1")
      (footprint "LED-1")
      (description "Typical RED GaAs LED")
      (fields (field (name "PUBLISHER") "Altium Limited"))
      (libsource (lib "Miscellaneous Devices") (part "LED1"))
    )
    (comp (ref "D164")
      (value "LED1")
      (footprint "LED-1")
      (description "Typical RED GaAs LED")
      (fields (field (name "PUBLISHER") "Altium Limited"))
      (libsource (lib "Miscellaneous Devices") (part "LED1"))
    )
    (comp (ref "D165")
      (value "LED1")
      (footprint "LED-1")
      (description "Typical RED GaAs LED")
      (fields (field (name "PUBLISHER") "Altium Limited"))
      (libsource (lib "Miscellaneous Devices") (part "LED1"))
    )
    (comp (ref "D166")
      (value "LED1")
      (footprint "LED-1")
      (description "Typical RED GaAs LED")
      (fields (field (name "PUBLISHER") "Altium Limited"))
      (libsource (lib "Miscellaneous Devices") (part "LED1"))
    )
    (comp (ref "D167")
      (value "LED1")
      (footprint "LED-1")
      (description "Typical RED GaAs LED")
      (fields (field (name "PUBLISHER") "Altium Limited"))
      (libsource (lib "Miscellaneous Devices") (part "LED1"))
    )
    (comp (ref "D168")
      (value "LED1")
      (footprint "LED-1")
      (description "Typical RED GaAs LED")
      (fields (field (name "PUBLISHER") "Altium Limited"))
      (libsource (lib "Miscellaneous Devices") (part "LED1"))
    )
    (comp (ref "D169")
      (value "LED1")
      (footprint "LED-1")
      (description "Typical RED GaAs LED")
      (fields (field (name "PUBLISHER") "Altium Limited"))
      (libsource (lib "Miscellaneous Devices") (part "LED1"))
    )
    (comp (ref "D170")
      (value "LED1")
      (footprint "LED-1")
      (description "Typical RED GaAs LED")
      (fields (field (name "PUBLISHER") "Altium Limited"))
      (libsource (lib "Miscellaneous Devices") (part "LED1"))
    )
    (comp (ref "D171")
      (value "LED1")
      (footprint "LED-1")
      (description "Typical RED GaAs LED")
      (fields (field (name "PUBLISHER") "Altium Limited"))
      (libsource (lib "Miscellaneous Devices") (part "LED1"))
    )
    (comp (ref "D172")
      (value "LED1")
      (footprint "LED-1")
      (description "Typical RED GaAs LED")
      (fields (field (name "PUBLISHER") "Altium Limited"))
      (libsource (lib "Miscellaneous Devices") (part "LED1"))
    )
    (comp (ref "D173")
      (value "LED1")
      (footprint "LED-1")
      (description "Typical RED GaAs LED")
      (fields (field (name "PUBLISHER") "Altium Limited"))
      (libsource (lib "Miscellaneous Devices") (part "LED1"))
    )
    (comp (ref "D174")
      (value "LED1")
      (footprint "LED-1")
      (description "Typical RED GaAs LED")
      (fields (field (name "PUBLISHER") "Altium Limited"))
      (libsource (lib "Miscellaneous Devices") (part "LED1"))
    )
    (comp (ref "D175")
      (value "LED1")
      (footprint "LED-1")
      (description "Typical RED GaAs LED")
      (fields (field (name "PUBLISHER") "Altium Limited"))
      (libsource (lib "Miscellaneous Devices") (part "LED1"))
    )
    (comp (ref "D176")
      (value "LED1")
      (footprint "LED-1")
      (description "Typical RED GaAs LED")
      (fields (field (name "PUBLISHER") "Altium Limited"))
      (libsource (lib "Miscellaneous Devices") (part "LED1"))
    )
    (comp (ref "D177")
      (value "LED1")
      (footprint "LED-1")
      (description "Typical RED GaAs LED")
      (fields (field (name "PUBLISHER") "Altium Limited"))
      (libsource (lib "Miscellaneous Devices") (part "LED1"))
    )
    (comp (ref "D178")
      (value "LED1")
      (footprint "LED-1")
      (description "Typical RED GaAs LED")
      (fields (field (name "PUBLISHER") "Altium Limited"))
      (libsource (lib "Miscellaneous Devices") (part "LED1"))
    )
    (comp (ref "D179")
      (value "LED1")
      (footprint "LED-1")
      (description "Typical RED GaAs LED")
      (fields (field (name "PUBLISHER") "Altium Limited"))
      (libsource (lib "Miscellaneous Devices") (part "LED1"))
    )
    (comp (ref "D180")
      (value "LED1")
      (footprint "LED-1")
      (description "Typical RED GaAs LED")
      (fields (field (name "PUBLISHER") "Altium Limited"))
      (libsource (lib "Miscellaneous Devices") (part "LED1"))
    )
    (comp (ref "D181")
      (value "LED1")
      (footprint "LED-1")
      (description "Typical RED GaAs LED")
      (fields (field (name "PUBLISHER") "Altium Limited"))
      (libsource (lib "Miscellaneous Devices") (part "LED1"))
    )
    (comp (ref "D182")
      (value "LED1")
      (footprint "LED-1")
      (description "Typical RED GaAs LED")
      (fields (field (name "PUBLISHER") "Altium Limited"))
      (libsource (lib "Miscellaneous Devices") (part "LED1"))
    )
    (comp (ref "D183")
      (value "LED1")
      (footprint "LED-1")
      (description "Typical RED GaAs LED")
      (fields (field (name "PUBLISHER") "Altium Limited"))
      (libsource (lib "Miscellaneous Devices") (part "LED1"))
    )
    (comp (ref "D184")
      (value "LED1")
      (footprint "LED-1")
      (description "Typical RED GaAs LED")
      (fields (field (name "PUBLISHER") "Altium Limited"))
      (libsource (lib "Miscellaneous Devices") (part "LED1"))
    )
    (comp (ref "D185")
      (value "LED1")
      (footprint "LED-1")
      (description "Typical RED GaAs LED")
      (fields (field (name "PUBLISHER") "Altium Limited"))
      (libsource (lib "Miscellaneous Devices") (part "LED1"))
    )
    (comp (ref "D186")
      (value "LED1")
      (footprint "LED-1")
      (description "Typical RED GaAs LED")
      (fields (field (name "PUBLISHER") "Altium Limited"))
      (libsource (lib "Miscellaneous Devices") (part "LED1"))
    )
    (comp (ref "D187")
      (value "LED1")
      (footprint "LED-1")
      (description "Typical RED GaAs LED")
      (fields (field (name "PUBLISHER") "Altium Limited"))
      (libsource (lib "Miscellaneous Devices") (part "LED1"))
    )
    (comp (ref "D188")
      (value "LED1")
      (footprint "LED-1")
      (description "Typical RED GaAs LED")
      (fields (field (name "PUBLISHER") "Altium Limited"))
      (libsource (lib "Miscellaneous Devices") (part "LED1"))
    )
    (comp (ref "D189")
      (value "LED1")
      (footprint "LED-1")
      (description "Typical RED GaAs LED")
      (fields (field (name "PUBLISHER") "Altium Limited"))
      (libsource (lib "Miscellaneous Devices") (part "LED1"))
    )
    (comp (ref "D190")
      (value "LED1")
      (footprint "LED-1")
      (description "Typical RED GaAs LED")
      (fields (field (name "PUBLISHER") "Altium Limited"))
      (libsource (lib "Miscellaneous Devices") (part "LED1"))
    )
    (comp (ref "D191")
      (value "LED1")
      (footprint "LED-1")
      (description "Typical RED GaAs LED")
      (fields (field (name "PUBLISHER") "Altium Limited"))
      (libsource (lib "Miscellaneous Devices") (part "LED1"))
    )
    (comp (ref "D192")
      (value "LED1")
      (footprint "LED-1")
      (description "Typical RED GaAs LED")
      (fields (field (name "PUBLISHER") "Altium Limited"))
      (libsource (lib "Miscellaneous Devices") (part "LED1"))
    )
    (comp (ref "D193")
      (value "LED1")
      (footprint "LED-1")
      (description "Typical RED GaAs LED")
      (fields (field (name "PUBLISHER") "Altium Limited"))
      (libsource (lib "Miscellaneous Devices") (part "LED1"))
    )
    (comp (ref "D194")
      (value "LED1")
      (footprint "LED-1")
      (description "Typical RED GaAs LED")
      (fields (field (name "PUBLISHER") "Altium Limited"))
      (libsource (lib "Miscellaneous Devices") (part "LED1"))
    )
    (comp (ref "D195")
      (value "LED1")
      (footprint "LED-1")
      (description "Typical RED GaAs LED")
      (fields (field (name "PUBLISHER") "Altium Limited"))
      (libsource (lib "Miscellaneous Devices") (part "LED1"))
    )
    (comp (ref "D196")
      (value "LED1")
      (footprint "LED-1")
      (description "Typical RED GaAs LED")
      (fields (field (name "PUBLISHER") "Altium Limited"))
      (libsource (lib "Miscellaneous Devices") (part "LED1"))
    )
    (comp (ref "D197")
      (value "LED1")
      (footprint "LED-1")
      (description "Typical RED GaAs LED")
      (fields (field (name "PUBLISHER") "Altium Limited"))
      (libsource (lib "Miscellaneous Devices") (part "LED1"))
    )
    (comp (ref "D198")
      (value "LED1")
      (footprint "LED-1")
      (description "Typical RED GaAs LED")
      (fields (field (name "PUBLISHER") "Altium Limited"))
      (libsource (lib "Miscellaneous Devices") (part "LED1"))
    )
    (comp (ref "D199")
      (value "LED1")
      (footprint "LED-1")
      (description "Typical RED GaAs LED")
      (fields (field (name "PUBLISHER") "Altium Limited"))
      (libsource (lib "Miscellaneous Devices") (part "LED1"))
    )
    (comp (ref "D200")
      (value "LED1")
      (footprint "LED-1")
      (description "Typical RED GaAs LED")
      (fields (field (name "PUBLISHER") "Altium Limited"))
      (libsource (lib "Miscellaneous Devices") (part "LED1"))
    )
    (comp (ref "D201")
      (value "LED1")
      (footprint "LED-1")
      (description "Typical RED GaAs LED")
      (fields (field (name "PUBLISHER") "Altium Limited"))
      (libsource (lib "Miscellaneous Devices") (part "LED1"))
    )
    (comp (ref "D202")
      (value "LED1")
      (footprint "LED-1")
      (description "Typical RED GaAs LED")
      (fields (field (name "PUBLISHER") "Altium Limited"))
      (libsource (lib "Miscellaneous Devices") (part "LED1"))
    )
    (comp (ref "D203")
      (value "LED1")
      (footprint "LED-1")
      (description "Typical RED GaAs LED")
      (fields (field (name "PUBLISHER") "Altium Limited"))
      (libsource (lib "Miscellaneous Devices") (part "LED1"))
    )
    (comp (ref "D204")
      (value "LED1")
      (footprint "LED-1")
      (description "Typical RED GaAs LED")
      (fields (field (name "PUBLISHER") "Altium Limited"))
      (libsource (lib "Miscellaneous Devices") (part "LED1"))
    )
    (comp (ref "D205")
      (value "LED1")
      (footprint "LED-1")
      (description "Typical RED GaAs LED")
      (fields (field (name "PUBLISHER") "Altium Limited"))
      (libsource (lib "Miscellaneous Devices") (part "LED1"))
    )
    (comp (ref "D206")
      (value "LED1")
      (footprint "LED-1")
      (description "Typical RED GaAs LED")
      (fields (field (name "PUBLISHER") "Altium Limited"))
      (libsource (lib "Miscellaneous Devices") (part "LED1"))
    )
    (comp (ref "D207")
      (value "LED1")
      (footprint "LED-1")
      (description "Typical RED GaAs LED")
      (fields (field (name "PUBLISHER") "Altium Limited"))
      (libsource (lib "Miscellaneous Devices") (part "LED1"))
    )
    (comp (ref "D208")
      (value "LED1")
      (footprint "LED-1")
      (description "Typical RED GaAs LED")
      (fields (field (name "PUBLISHER") "Altium Limited"))
      (libsource (lib "Miscellaneous Devices") (part "LED1"))
    )
    (comp (ref "D209")
      (value "LED1")
      (footprint "LED-1")
      (description "Typical RED GaAs LED")
      (fields (field (name "PUBLISHER") "Altium Limited"))
      (libsource (lib "Miscellaneous Devices") (part "LED1"))
    )
    (comp (ref "D210")
      (value "LED1")
      (footprint "LED-1")
      (description "Typical RED GaAs LED")
      (fields (field (name "PUBLISHER") "Altium Limited"))
      (libsource (lib "Miscellaneous Devices") (part "LED1"))
    )
    (comp (ref "D211")
      (value "LED1")
      (footprint "LED-1")
      (description "Typical RED GaAs LED")
      (fields (field (name "PUBLISHER") "Altium Limited"))
      (libsource (lib "Miscellaneous Devices") (part "LED1"))
    )
    (comp (ref "D212")
      (value "LED1")
      (footprint "LED-1")
      (description "Typical RED GaAs LED")
      (fields (field (name "PUBLISHER") "Altium Limited"))
      (libsource (lib "Miscellaneous Devices") (part "LED1"))
    )
    (comp (ref "D213")
      (value "LED1")
      (footprint "LED-1")
      (description "Typical RED GaAs LED")
      (fields (field (name "PUBLISHER") "Altium Limited"))
      (libsource (lib "Miscellaneous Devices") (part "LED1"))
    )
    (comp (ref "D214")
      (value "LED1")
      (footprint "LED-1")
      (description "Typical RED GaAs LED")
      (fields (field (name "PUBLISHER") "Altium Limited"))
      (libsource (lib "Miscellaneous Devices") (part "LED1"))
    )
    (comp (ref "D215")
      (value "LED1")
      (footprint "LED-1")
      (description "Typical RED GaAs LED")
      (fields (field (name "PUBLISHER") "Altium Limited"))
      (libsource (lib "Miscellaneous Devices") (part "LED1"))
    )
    (comp (ref "D216")
      (value "LED1")
      (footprint "LED-1")
      (description "Typical RED GaAs LED")
      (fields (field (name "PUBLISHER") "Altium Limited"))
      (libsource (lib "Miscellaneous Devices") (part "LED1"))
    )
    (comp (ref "D217")
      (value "LED1")
      (footprint "LED-1")
      (description "Typical RED GaAs LED")
      (fields (field (name "PUBLISHER") "Altium Limited"))
      (libsource (lib "Miscellaneous Devices") (part "LED1"))
    )
    (comp (ref "D218")
      (value "LED1")
      (footprint "LED-1")
      (description "Typical RED GaAs LED")
      (fields (field (name "PUBLISHER") "Altium Limited"))
      (libsource (lib "Miscellaneous Devices") (part "LED1"))
    )
    (comp (ref "D219")
      (value "LED1")
      (footprint "LED-1")
      (description "Typical RED GaAs LED")
      (fields (field (name "PUBLISHER") "Altium Limited"))
      (libsource (lib "Miscellaneous Devices") (part "LED1"))
    )
    (comp (ref "D220")
      (value "LED1")
      (footprint "LED-1")
      (description "Typical RED GaAs LED")
      (fields (field (name "PUBLISHER") "Altium Limited"))
      (libsource (lib "Miscellaneous Devices") (part "LED1"))
    )
    (comp (ref "D221")
      (value "LED1")
      (footprint "LED-1")
      (description "Typical RED GaAs LED")
      (fields (field (name "PUBLISHER") "Altium Limited"))
      (libsource (lib "Miscellaneous Devices") (part "LED1"))
    )
    (comp (ref "D222")
      (value "LED1")
      (footprint "LED-1")
      (description "Typical RED GaAs LED")
      (fields (field (name "PUBLISHER") "Altium Limited"))
      (libsource (lib "Miscellaneous Devices") (part "LED1"))
    )
    (comp (ref "D223")
      (value "LED1")
      (footprint "LED-1")
      (description "Typical RED GaAs LED")
      (fields (field (name "PUBLISHER") "Altium Limited"))
      (libsource (lib "Miscellaneous Devices") (part "LED1"))
    )
    (comp (ref "D224")
      (value "LED1")
      (footprint "LED-1")
      (description "Typical RED GaAs LED")
      (fields (field (name "PUBLISHER") "Altium Limited"))
      (libsource (lib "Miscellaneous Devices") (part "LED1"))
    )
    (comp (ref "D225")
      (value "LED1")
      (footprint "LED-1")
      (description "Typical RED GaAs LED")
      (fields (field (name "PUBLISHER") "Altium Limited"))
      (libsource (lib "Miscellaneous Devices") (part "LED1"))
    )
    (comp (ref "D226")
      (value "LED1")
      (footprint "LED-1")
      (description "Typical RED GaAs LED")
      (fields (field (name "PUBLISHER") "Altium Limited"))
      (libsource (lib "Miscellaneous Devices") (part "LED1"))
    )
    (comp (ref "D227")
      (value "LED1")
      (footprint "LED-1")
      (description "Typical RED GaAs LED")
      (fields (field (name "PUBLISHER") "Altium Limited"))
      (libsource (lib "Miscellaneous Devices") (part "LED1"))
    )
    (comp (ref "D228")
      (value "LED1")
      (footprint "LED-1")
      (description "Typical RED GaAs LED")
      (fields (field (name "PUBLISHER") "Altium Limited"))
      (libsource (lib "Miscellaneous Devices") (part "LED1"))
    )
    (comp (ref "D229")
      (value "LED1")
      (footprint "LED-1")
      (description "Typical RED GaAs LED")
      (fields (field (name "PUBLISHER") "Altium Limited"))
      (libsource (lib "Miscellaneous Devices") (part "LED1"))
    )
    (comp (ref "D230")
      (value "LED1")
      (footprint "LED-1")
      (description "Typical RED GaAs LED")
      (fields (field (name "PUBLISHER") "Altium Limited"))
      (libsource (lib "Miscellaneous Devices") (part "LED1"))
    )
    (comp (ref "D231")
      (value "LED1")
      (footprint "LED-1")
      (description "Typical RED GaAs LED")
      (fields (field (name "PUBLISHER") "Altium Limited"))
      (libsource (lib "Miscellaneous Devices") (part "LED1"))
    )
    (comp (ref "D232")
      (value "LED1")
      (footprint "LED-1")
      (description "Typical RED GaAs LED")
      (fields (field (name "PUBLISHER") "Altium Limited"))
      (libsource (lib "Miscellaneous Devices") (part "LED1"))
    )
    (comp (ref "D233")
      (value "LED1")
      (footprint "LED-1")
      (description "Typical RED GaAs LED")
      (fields (field (name "PUBLISHER") "Altium Limited"))
      (libsource (lib "Miscellaneous Devices") (part "LED1"))
    )
    (comp (ref "D234")
      (value "LED1")
      (footprint "LED-1")
      (description "Typical RED GaAs LED")
      (fields (field (name "PUBLISHER") "Altium Limited"))
      (libsource (lib "Miscellaneous Devices") (part "LED1"))
    )
    (comp (ref "D235")
      (value "LED1")
      (footprint "LED-1")
      (description "Typical RED GaAs LED")
      (fields (field (name "PUBLISHER") "Altium Limited"))
      (libsource (lib "Miscellaneous Devices") (part "LED1"))
    )
    (comp (ref "D236")
      (value "LED1")
      (footprint "LED-1")
      (description "Typical RED GaAs LED")
      (fields (field (name "PUBLISHER") "Altium Limited"))
      (libsource (lib "Miscellaneous Devices") (part "LED1"))
    )
    (comp (ref "D237")
      (value "LED1")
      (footprint "LED-1")
      (description "Typical RED GaAs LED")
      (fields (field (name "PUBLISHER") "Altium Limited"))
      (libsource (lib "Miscellaneous Devices") (part "LED1"))
    )
    (comp (ref "D238")
      (value "LED1")
      (footprint "LED-1")
      (description "Typical RED GaAs LED")
      (fields (field (name "PUBLISHER") "Altium Limited"))
      (libsource (lib "Miscellaneous Devices") (part "LED1"))
    )
    (comp (ref "D239")
      (value "LED1")
      (footprint "LED-1")
      (description "Typical RED GaAs LED")
      (fields (field (name "PUBLISHER") "Altium Limited"))
      (libsource (lib "Miscellaneous Devices") (part "LED1"))
    )
    (comp (ref "D240")
      (value "LED1")
      (footprint "LED-1")
      (description "Typical RED GaAs LED")
      (fields (field (name "PUBLISHER") "Altium Limited"))
      (libsource (lib "Miscellaneous Devices") (part "LED1"))
    )
    (comp (ref "D241")
      (value "LED1")
      (footprint "LED-1")
      (description "Typical RED GaAs LED")
      (fields (field (name "PUBLISHER") "Altium Limited"))
      (libsource (lib "Miscellaneous Devices") (part "LED1"))
    )
    (comp (ref "D242")
      (value "LED1")
      (footprint "LED-1")
      (description "Typical RED GaAs LED")
      (fields (field (name "PUBLISHER") "Altium Limited"))
      (libsource (lib "Miscellaneous Devices") (part "LED1"))
    )
    (comp (ref "D243")
      (value "LED1")
      (footprint "LED-1")
      (description "Typical RED GaAs LED")
      (fields (field (name "PUBLISHER") "Altium Limited"))
      (libsource (lib "Miscellaneous Devices") (part "LED1"))
    )
    (comp (ref "D244")
      (value "LED1")
      (footprint "LED-1")
      (description "Typical RED GaAs LED")
      (fields (field (name "PUBLISHER") "Altium Limited"))
      (libsource (lib "Miscellaneous Devices") (part "LED1"))
    )
    (comp (ref "D245")
      (value "LED1")
      (footprint "LED-1")
      (description "Typical RED GaAs LED")
      (fields (field (name "PUBLISHER") "Altium Limited"))
      (libsource (lib "Miscellaneous Devices") (part "LED1"))
    )
    (comp (ref "D246")
      (value "LED1")
      (footprint "LED-1")
      (description "Typical RED GaAs LED")
      (fields (field (name "PUBLISHER") "Altium Limited"))
      (libsource (lib "Miscellaneous Devices") (part "LED1"))
    )
    (comp (ref "D247")
      (value "LED1")
      (footprint "LED-1")
      (description "Typical RED GaAs LED")
      (fields (field (name "PUBLISHER") "Altium Limited"))
      (libsource (lib "Miscellaneous Devices") (part "LED1"))
    )
    (comp (ref "D248")
      (value "LED1")
      (footprint "LED-1")
      (description "Typical RED GaAs LED")
      (fields (field (name "PUBLISHER") "Altium Limited"))
      (libsource (lib "Miscellaneous Devices") (part "LED1"))
    )
    (comp (ref "D249")
      (value "LED1")
      (footprint "LED-1")
      (description "Typical RED GaAs LED")
      (fields (field (name "PUBLISHER") "Altium Limited"))
      (libsource (lib "Miscellaneous Devices") (part "LED1"))
    )
    (comp (ref "D250")
      (value "LED1")
      (footprint "LED-1")
      (description "Typical RED GaAs LED")
      (fields (field (name "PUBLISHER") "Altium Limited"))
      (libsource (lib "Miscellaneous Devices") (part "LED1"))
    )
    (comp (ref "D251")
      (value "LED1")
      (footprint "LED-1")
      (description "Typical RED GaAs LED")
      (fields (field (name "PUBLISHER") "Altium Limited"))
      (libsource (lib "Miscellaneous Devices") (part "LED1"))
    )
    (comp (ref "D252")
      (value "LED1")
      (footprint "LED-1")
      (description "Typical RED GaAs LED")
      (fields (field (name "PUBLISHER") "Altium Limited"))
      (libsource (lib "Miscellaneous Devices") (part "LED1"))
    )
    (comp (ref "D253")
      (value "LED1")
      (footprint "LED-1")
      (description "Typical RED GaAs LED")
      (fields (field (name "PUBLISHER") "Altium Limited"))
      (libsource (lib "Miscellaneous Devices") (part "LED1"))
    )
    (comp (ref "D254")
      (value "LED1")
      (footprint "LED-1")
      (description "Typical RED GaAs LED")
      (fields (field (name "PUBLISHER") "Altium Limited"))
      (libsource (lib "Miscellaneous Devices") (part "LED1"))
    )
    (comp (ref "D255")
      (value "LED1")
      (footprint "LED-1")
      (description "Typical RED GaAs LED")
      (fields (field (name "PUBLISHER") "Altium Limited"))
      (libsource (lib "Miscellaneous Devices") (part "LED1"))
    )
    (comp (ref "D256")
      (value "LED1")
      (footprint "LED-1")
      (description "Typical RED GaAs LED")
      (fields (field (name "PUBLISHER") "Altium Limited"))
      (libsource (lib "Miscellaneous Devices") (part "LED1"))
    )
    (comp (ref "Driver1")
      (value "SW DIP-7")
      (footprint "DIP-14")
      (description "DIP Switch, 7 Position, SPST")
      (fields (field (name "PUBLISHER") "Altium Limited"))
      (libsource (lib "Miscellaneous Devices") (part "SW DIP-7"))
    )
    (comp (ref "Driver2")
      (value "SW DIP-7")
      (footprint "DIP-14")
      (description "DIP Switch, 7 Position, SPST")
      (fields (field (name "PUBLISHER") "Altium Limited"))
      (libsource (lib "Miscellaneous Devices") (part "SW DIP-7"))
    )
    (comp (ref "Driver3")
      (value "SW DIP-7")
      (footprint "DIP-14")
      (description "DIP Switch, 7 Position, SPST")
      (fields (field (name "PUBLISHER") "Altium Limited"))
      (libsource (lib "Miscellaneous Devices") (part "SW DIP-7"))
    )
    (comp (ref "Driver4")
      (value "SW DIP-7")
      (footprint "DIP-14")
      (description "DIP Switch, 7 Position, SPST")
      (fields (field (name "PUBLISHER") "Altium Limited"))
      (libsource (lib "Miscellaneous Devices") (part "SW DIP-7"))
    )
    (comp (ref "DémuxBas")
      (value "SW DIP-6")
      (footprint "DIP-12/SW")
      (description "DIP Switch, 6 Position, SPST")
      (fields (field (name "PUBLISHER") "Altium Limited"))
      (libsource (lib "Miscellaneous Devices") (part "SW DIP-6"))
    )
    (comp (ref "DémuxHaut")
      (value "SW DIP-6")
      (footprint "DIP-12/SW")
      (description "DIP Switch, 6 Position, SPST")
      (fields (field (name "PUBLISHER") "Altium Limited"))
      (libsource (lib "Miscellaneous Devices") (part "SW DIP-6"))
    )
    (comp (ref "IC*1")
      (value "dsPIC33FJ128MC802")
      (footprint "SPDIP300-SP28")
      (libsource (lib "lib_robotronik26092013") (part "dsPIC33FJ128MC802"))
    )
    (comp (ref "PGC")
      (value "Header 2")
      (footprint "HDR1X2")
      (description "Header, 2-Pin")
      (fields (field (name "PUBLISHER") "Altium Limited"))
      (libsource (lib "Miscellaneous Connectors") (part "Header 2"))
    )
    (comp (ref "PGD")
      (value "Header 2")
      (footprint "HDR1X2")
      (description "Header, 2-Pin")
      (fields (field (name "PUBLISHER") "Altium Limited"))
      (libsource (lib "Miscellaneous Connectors") (part "Header 2"))
    )
    (comp (ref "pickit")
      (value "pickit3")
      (footprint "HDR1X5")
      (libsource (lib "lib_Robotronik") (part "pickit3"))
    )
    (comp (ref "R1")
      (value "1kohm")
      (footprint "AXIAL-0.5")
      (libsource (lib "lib_robotronik26092013") (part "Resistance"))
    )
    (comp (ref "R2")
      (value "1kohm")
      (footprint "AXIAL-0.5")
      (libsource (lib "lib_robotronik26092013") (part "Resistance"))
    )
    (comp (ref "R3")
      (value "1kohm")
      (footprint "AXIAL-0.5")
      (libsource (lib "lib_robotronik26092013") (part "Resistance"))
    )
    (comp (ref "R4")
      (value "1kohm")
      (footprint "AXIAL-0.5")
      (libsource (lib "lib_robotronik26092013") (part "Resistance"))
    )
    (comp (ref "R9")
      (value "10kohm")
      (footprint "AXIAL-0.5")
      (libsource (lib "lib_robotronik26092013") (part "Resistance"))
    )
    (comp (ref "Regul3V3")
      (value "Bornier_3")
      (footprint "D2PAK_N")
      (description "Header, 3-Pin")
      (fields (field (name "PUBLISHER") "Altium Limited"))
      (libsource (lib "INTEGRATED_LIBRARY1_CONNECTEURS") (part "Bornier_3"))
    )
  )
  (nets
    (net (code "1") (name "/MCLR") (class "Default")
      (node (ref "C4") (pin "2") (pinfunction "2_2") (pintype "passive"))
      (node (ref "IC*1") (pin "1") (pinfunction "MCLR_1") (pintype "passive"))
      (node (ref "R9") (pin "1") (pinfunction "1_1") (pintype "passive"))
      (node (ref "pickit") (pin "1") (pinfunction "Vpp/MCLR_1") (pintype "passive"))
    )
    (net (code "2") (name "/PGC") (class "Default")
      (node (ref "IC*1") (pin "5") (pinfunction "RB1_5") (pintype "passive"))
      (node (ref "PGC") (pin "1") (pinfunction "1_1") (pintype "passive"))
      (node (ref "pickit") (pin "5") (pinfunction "PGC_5") (pintype "passive"))
    )
    (net (code "3") (name "/PGD") (class "Default")
      (node (ref "IC*1") (pin "4") (pinfunction "RB0_4") (pintype "passive"))
      (node (ref "PGD") (pin "1") (pinfunction "1_1") (pintype "passive"))
      (node (ref "pickit") (pin "4") (pinfunction "PGD_4") (pintype "passive"))
    )
    (net (code "4") (name "/RA0") (class "Default")
      (node (ref "IC*1") (pin "2") (pinfunction "RA0_2") (pintype "passive"))
      (node (ref "R1") (pin "2") (pinfunction "2_2") (pintype "passive"))
    )
    (net (code "5") (name "/RA1") (class "Default")
      (node (ref "IC*1") (pin "3") (pinfunction "RA1_3") (pintype "passive"))
      (node (ref "R2") (pin "2") (pinfunction "2_2") (pintype "passive"))
    )
    (net (code "6") (name "/RA2") (class "Default")
      (node (ref "7") (pin "2") (pinfunction "2_2") (pintype "passive"))
      (node (ref "IC*1") (pin "9") (pinfunction "RA2_9") (pintype "passive"))
    )
    (net (code "7") (name "/RA3") (class "Default")
      (node (ref "8") (pin "2") (pinfunction "2_2") (pintype "passive"))
      (node (ref "IC*1") (pin "10") (pinfunction "RA3_10") (pintype "passive"))
    )
    (net (code "8") (name "/RA4") (class "Default")
      (node (ref "10") (pin "2") (pinfunction "2_2") (pintype "passive"))
      (node (ref "IC*1") (pin "12") (pinfunction "RA4_12") (pintype "passive"))
    )
    (net (code "9") (name "/RB0") (class "Default")
      (node (ref "PGD") (pin "2") (pinfunction "2_2") (pintype "passive"))
      (node (ref "R3") (pin "2") (pinfunction "2_2") (pintype "passive"))
    )
    (net (code "10") (name "/RB1") (class "Default")
      (node (ref "PGC") (pin "2") (pinfunction "2_2") (pintype "passive"))
      (node (ref "R4") (pin "2") (pinfunction "2_2") (pintype "passive"))
    )
    (net (code "11") (name "/RB2") (class "Default")
      (node (ref "5") (pin "2") (pinfunction "2_2") (pintype "passive"))
      (node (ref "IC*1") (pin "6") (pinfunction "RB2_6") (pintype "passive"))
    )
    (net (code "12") (name "/RB3") (class "Default")
      (node (ref "6") (pin "2") (pinfunction "2_2") (pintype "passive"))
      (node (ref "IC*1") (pin "7") (pinfunction "RB3_7") (pintype "passive"))
    )
    (net (code "13") (name "/RB4") (class "Default")
      (node (ref "9") (pin "2") (pinfunction "2_2") (pintype "passive"))
      (node (ref "IC*1") (pin "11") (pinfunction "RB4_11") (pintype "passive"))
    )
    (net (code "14") (name "/RB5") (class "Default")
      (node (ref "11") (pin "2") (pinfunction "2_2") (pintype "passive"))
      (node (ref "IC*1") (pin "14") (pinfunction "RB5_14") (pintype "passive"))
    )
    (net (code "15") (name "/RB6") (class "Default")
      (node (ref "12") (pin "2") (pinfunction "2_2") (pintype "passive"))
      (node (ref "IC*1") (pin "15") (pinfunction "RB6_15") (pintype "passive"))
    )
    (net (code "16") (name "/RB7") (class "Default")
      (node (ref "13") (pin "2") (pinfunction "2_2") (pintype "passive"))
      (node (ref "IC*1") (pin "16") (pinfunction "RB7_16") (pintype "passive"))
    )
    (net (code "17") (name "/RB8") (class "Default")
      (node (ref "14") (pin "2") (pinfunction "2_2") (pintype "passive"))
      (node (ref "IC*1") (pin "17") (pinfunction "RB8_17") (pintype "passive"))
    )
    (net (code "18") (name "/RB9") (class "Default")
      (node (ref "15") (pin "2") (pinfunction "2_2") (pintype "passive"))
      (node (ref "IC*1") (pin "18") (pinfunction "RB9_18") (pintype "passive"))
    )
    (net (code "19") (name "/RB10") (class "Default")
      (node (ref "16") (pin "2") (pinfunction "2_2") (pintype "passive"))
      (node (ref "IC*1") (pin "21") (pinfunction "RB10_21") (pintype "passive"))
    )
    (net (code "20") (name "3.3V") (class "Default")
      (node (ref "C12") (pin "2") (pinfunction "2_2") (pintype "passive"))
      (node (ref "DémuxHaut") (pin "12") (pinfunction "B1_12") (pintype "passive"))
      (node (ref "IC*1") (pin "13") (pinfunction "Vdd_13") (pintype "passive"))
      (node (ref "IC*1") (pin "28") (pinfunction "AVdd_28") (pintype "passive"))
      (node (ref "R9") (pin "2") (pinfunction "2_2") (pintype "passive"))
      (node (ref "Regul3V3") (pin "3") (pinfunction "3_3") (pintype "passive"))
      (node (ref "pickit") (pin "2") (pinfunction "Vdd_2") (pintype "passive"))
    )
    (net (code "21") (name "5V") (class "Default")
      (node (ref "12V") (pin "1") (pinfunction "1_1") (pintype "passive"))
      (node (ref "C1") (pin "1") (pinfunction "1_1") (pintype "passive"))
      (node (ref "Driver1") (pin "14") (pinfunction "B1_14") (pintype "passive"))
      (node (ref "Driver1") (pin "2") (pinfunction "A2_2") (pintype "passive"))
      (node (ref "Driver1") (pin "4") (pinfunction "A4_4") (pintype "passive"))
      (node (ref "Driver1") (pin "6") (pinfunction "A6_6") (pintype "passive"))
      (node (ref "Driver1") (pin "9") (pinfunction "B6_9") (pintype "passive"))
      (node (ref "Driver2") (pin "14") (pinfunction "B1_14") (pintype "passive"))
      (node (ref "Driver2") (pin "2") (pinfunction "A2_2") (pintype "passive"))
      (node (ref "Driver2") (pin "4") (pinfunction "A4_4") (pintype "passive"))
      (node (ref "Driver2") (pin "6") (pinfunction "A6_6") (pintype "passive"))
      (node (ref "Driver2") (pin "9") (pinfunction "B6_9") (pintype "passive"))
      (node (ref "Driver3") (pin "14") (pinfunction "B1_14") (pintype "passive"))
      (node (ref "Driver3") (pin "2") (pinfunction "A2_2") (pintype "passive"))
      (node (ref "Driver3") (pin "4") (pinfunction "A4_4") (pintype "passive"))
      (node (ref "Driver3") (pin "6") (pinfunction "A6_6") (pintype "passive"))
      (node (ref "Driver3") (pin "9") (pinfunction "B6_9") (pintype "passive"))
      (node (ref "Driver4") (pin "14") (pinfunction "B1_14") (pintype "passive"))
      (node (ref "Driver4") (pin "2") (pinfunction "A2_2") (pintype "passive"))
      (node (ref "Driver4") (pin "4") (pinfunction "A4_4") (pintype "passive"))
      (node (ref "Driver4") (pin "6") (pinfunction "A6_6") (pintype "passive"))
      (node (ref "Driver4") (pin "9") (pinfunction "B6_9") (pintype "passive"))
      (node (ref "Regul3V3") (pin "1") (pinfunction "1_1") (pintype "passive"))
    )
    (net (code "22") (name "GND") (class "Default")
      (node (ref "12V") (pin "2") (pinfunction "2_2") (pintype "passive"))
      (node (ref "C1") (pin "2") (pinfunction "2_2") (pintype "passive"))
      (node (ref "C12") (pin "1") (pinfunction "1_1") (pintype "passive"))
      (node (ref "C4") (pin "1") (pinfunction "1_1") (pintype "passive"))
      (node (ref "C5") (pin "2") (pinfunction "2_2") (pintype "passive"))
      (node (ref "Driver1") (pin "7") (pinfunction "A7_7") (pintype "passive"))
      (node (ref "Driver2") (pin "7") (pinfunction "A7_7") (pintype "passive"))
      (node (ref "Driver3") (pin "7") (pinfunction "A7_7") (pintype "passive"))
      (node (ref "Driver4") (pin "7") (pinfunction "A7_7") (pintype "passive"))
      (node (ref "DémuxBas") (pin "6") (pinfunction "A6_6") (pintype "passive"))
      (node (ref "IC*1") (pin "19") (pinfunction "Vss_19") (pintype "passive"))
      (node (ref "IC*1") (pin "27") (pinfunction "AVss_27") (pintype "passive"))
      (node (ref "IC*1") (pin "8") (pinfunction "Vss_8") (pintype "passive"))
      (node (ref "Regul3V3") (pin "2") (pinfunction "2_2") (pintype "passive"))
      (node (ref "pickit") (pin "3") (pinfunction "Vss_3") (pintype "passive"))
    )
    (net (code "23") (name "Net-(D1-A)") (class "Default")
      (node (ref "D1") (pin "1") (pinfunction "A_1") (pintype "passive"))
      (node (ref "D113") (pin "1") (pinfunction "A_1") (pintype "passive"))
      (node (ref "D129") (pin "1") (pinfunction "A_1") (pintype "passive"))
      (node (ref "D145") (pin "1") (pinfunction "A_1") (pintype "passive"))
      (node (ref "D161") (pin "1") (pinfunction "A_1") (pintype "passive"))
      (node (ref "D17") (pin "1") (pinfunction "A_1") (pintype "passive"))
      (node (ref "D177") (pin "1") (pinfunction "A_1") (pintype "passive"))
      (node (ref "D193") (pin "1") (pinfunction "A_1") (pintype "passive"))
      (node (ref "D209") (pin "1") (pinfunction "A_1") (pintype "passive"))
      (node (ref "D225") (pin "1") (pinfunction "A_1") (pintype "passive"))
      (node (ref "D241") (pin "1") (pinfunction "A_1") (pintype "passive"))
      (node (ref "D33") (pin "1") (pinfunction "A_1") (pintype "passive"))
      (node (ref "D49") (pin "1") (pinfunction "A_1") (pintype "passive"))
      (node (ref "D65") (pin "1") (pinfunction "A_1") (pintype "passive"))
      (node (ref "D81") (pin "1") (pinfunction "A_1") (pintype "passive"))
      (node (ref "D97") (pin "1") (pinfunction "A_1") (pintype "passive"))
      (node (ref "R1") (pin "1") (pinfunction "1_1") (pintype "passive"))
    )
    (net (code "24") (name "Net-(D1-K)") (class "Default")
      (node (ref "D1") (pin "2") (pinfunction "K_2") (pintype "passive"))
      (node (ref "D10") (pin "2") (pinfunction "K_2") (pintype "passive"))
      (node (ref "D11") (pin "2") (pinfunction "K_2") (pintype "passive"))
      (node (ref "D12") (pin "2") (pinfunction "K_2") (pintype "passive"))
      (node (ref "D13") (pin "2") (pinfunction "K_2") (pintype "passive"))
      (node (ref "D14") (pin "2") (pinfunction "K_2") (pintype "passive"))
      (node (ref "D15") (pin "2") (pinfunction "K_2") (pintype "passive"))
      (node (ref "D16") (pin "2") (pinfunction "K_2") (pintype "passive"))
      (node (ref "D2") (pin "2") (pinfunction "K_2") (pintype "passive"))
      (node (ref "D3") (pin "2") (pinfunction "K_2") (pintype "passive"))
      (node (ref "D4") (pin "2") (pinfunction "K_2") (pintype "passive"))
      (node (ref "D5") (pin "2") (pinfunction "K_2") (pintype "passive"))
      (node (ref "D6") (pin "2") (pinfunction "K_2") (pintype "passive"))
      (node (ref "D7") (pin "2") (pinfunction "K_2") (pintype "passive"))
      (node (ref "D8") (pin "2") (pinfunction "K_2") (pintype "passive"))
      (node (ref "D9") (pin "2") (pinfunction "K_2") (pintype "passive"))
      (node (ref "Driver1") (pin "10") (pinfunction "B5_10") (pintype "passive"))
    )
    (net (code "25") (name "Net-(D10-A)") (class "Default")
      (node (ref "10") (pin "1") (pinfunction "1_1") (pintype "passive"))
      (node (ref "D10") (pin "1") (pinfunction "A_1") (pintype "passive"))
      (node (ref "D106") (pin "1") (pinfunction "A_1") (pintype "passive"))
      (node (ref "D122") (pin "1") (pinfunction "A_1") (pintype "passive"))
      (node (ref "D138") (pin "1") (pinfunction "A_1") (pintype "passive"))
      (node (ref "D154") (pin "1") (pinfunction "A_1") (pintype "passive"))
      (node (ref "D170") (pin "1") (pinfunction "A_1") (pintype "passive"))
      (node (ref "D186") (pin "1") (pinfunction "A_1") (pintype "passive"))
      (node (ref "D202") (pin "1") (pinfunction "A_1") (pintype "passive"))
      (node (ref "D218") (pin "1") (pinfunction "A_1") (pintype "passive"))
      (node (ref "D234") (pin "1") (pinfunction "A_1") (pintype "passive"))
      (node (ref "D250") (pin "1") (pinfunction "A_1") (pintype "passive"))
      (node (ref "D26") (pin "1") (pinfunction "A_1") (pintype "passive"))
      (node (ref "D42") (pin "1") (pinfunction "A_1") (pintype "passive"))
      (node (ref "D58") (pin "1") (pinfunction "A_1") (pintype "passive"))
      (node (ref "D74") (pin "1") (pinfunction "A_1") (pintype "passive"))
      (node (ref "D90") (pin "1") (pinfunction "A_1") (pintype "passive"))
    )
    (net (code "26") (name "Net-(D17-K)") (class "Default")
      (node (ref "D17") (pin "2") (pinfunction "K_2") (pintype "passive"))
      (node (ref "D18") (pin "2") (pinfunction "K_2") (pintype "passive"))
      (node (ref "D19") (pin "2") (pinfunction "K_2") (pintype "passive"))
      (node (ref "D20") (pin "2") (pinfunction "K_2") (pintype "passive"))
      (node (ref "D21") (pin "2") (pinfunction "K_2") (pintype "passive"))
      (node (ref "D22") (pin "2") (pinfunction "K_2") (pintype "passive"))
      (node (ref "D23") (pin "2") (pinfunction "K_2") (pintype "passive"))
      (node (ref "D24") (pin "2") (pinfunction "K_2") (pintype "passive"))
      (node (ref "D25") (pin "2") (pinfunction "K_2") (pintype "passive"))
      (node (ref "D26") (pin "2") (pinfunction "K_2") (pintype "passive"))
      (node (ref "D27") (pin "2") (pinfunction "K_2") (pintype "passive"))
      (node (ref "D28") (pin "2") (pinfunction "K_2") (pintype "passive"))
      (node (ref "D29") (pin "2") (pinfunction "K_2") (pintype "passive"))
      (node (ref "D30") (pin "2") (pinfunction "K_2") (pintype "passive"))
      (node (ref "D31") (pin "2") (pinfunction "K_2") (pintype "passive"))
      (node (ref "D32") (pin "2") (pinfunction "K_2") (pintype "passive"))
      (node (ref "Driver1") (pin "11") (pinfunction "B4_11") (pintype "passive"))
    )
    (net (code "27") (name "Net-(D33-K)") (class "Default")
      (node (ref "D33") (pin "2") (pinfunction "K_2") (pintype "passive"))
      (node (ref "D34") (pin "2") (pinfunction "K_2") (pintype "passive"))
      (node (ref "D35") (pin "2") (pinfunction "K_2") (pintype "passive"))
      (node (ref "D36") (pin "2") (pinfunction "K_2") (pintype "passive"))
      (node (ref "D37") (pin "2") (pinfunction "K_2") (pintype "passive"))
      (node (ref "D38") (pin "2") (pinfunction "K_2") (pintype "passive"))
      (node (ref "D39") (pin "2") (pinfunction "K_2") (pintype "passive"))
      (node (ref "D40") (pin "2") (pinfunction "K_2") (pintype "passive"))
      (node (ref "D41") (pin "2") (pinfunction "K_2") (pintype "passive"))
      (node (ref "D42") (pin "2") (pinfunction "K_2") (pintype "passive"))
      (node (ref "D43") (pin "2") (pinfunction "K_2") (pintype "passive"))
      (node (ref "D44") (pin "2") (pinfunction "K_2") (pintype "passive"))
      (node (ref "D45") (pin "2") (pinfunction "K_2") (pintype "passive"))
      (node (ref "D46") (pin "2") (pinfunction "K_2") (pintype "passive"))
      (node (ref "D47") (pin "2") (pinfunction "K_2") (pintype "passive"))
      (node (ref "D48") (pin "2") (pinfunction "K_2") (pintype "passive"))
      (node (ref "Driver1") (pin "12") (pinfunction "B3_12") (pintype "passive"))
    )
    (net (code "28") (name "Net-(D49-K)") (class "Default")
      (node (ref "D49") (pin "2") (pinfunction "K_2") (pintype "passive"))
      (node (ref "D50") (pin "2") (pinfunction "K_2") (pintype "passive"))
      (node (ref "D51") (pin "2") (pinfunction "K_2") (pintype "passive"))
      (node (ref "D52") (pin "2") (pinfunction "K_2") (pintype "passive"))
      (node (ref "D53") (pin "2") (pinfunction "K_2") (pintype "passive"))
      (node (ref "D54") (pin "2") (pinfunction "K_2") (pintype "passive"))
      (node (ref "D55") (pin "2") (pinfunction "K_2") (pintype "passive"))
      (node (ref "D56") (pin "2") (pinfunction "K_2") (pintype "passive"))
      (node (ref "D57") (pin "2") (pinfunction "K_2") (pintype "passive"))
      (node (ref "D58") (pin "2") (pinfunction "K_2") (pintype "passive"))
      (node (ref "D59") (pin "2") (pinfunction "K_2") (pintype "passive"))
      (node (ref "D60") (pin "2") (pinfunction "K_2") (pintype "passive"))
      (node (ref "D61") (pin "2") (pinfunction "K_2") (pintype "passive"))
      (node (ref "D62") (pin "2") (pinfunction "K_2") (pintype "passive"))
      (node (ref "D63") (pin "2") (pinfunction "K_2") (pintype "passive"))
      (node (ref "D64") (pin "2") (pinfunction "K_2") (pintype "passive"))
      (node (ref "Driver1") (pin "13") (pinfunction "B2_13") (pintype "passive"))
    )
    (net (code "29") (name "Net-(D65-K)") (class "Default")
      (node (ref "D65") (pin "2") (pinfunction "K_2") (pintype "passive"))
      (node (ref "D66") (pin "2") (pinfunction "K_2") (pintype "passive"))
      (node (ref "D67") (pin "2") (pinfunction "K_2") (pintype "passive"))
      (node (ref "D68") (pin "2") (pinfunction "K_2") (pintype "passive"))
      (node (ref "D69") (pin "2") (pinfunction "K_2") (pintype "passive"))
      (node (ref "D70") (pin "2") (pinfunction "K_2") (pintype "passive"))
      (node (ref "D71") (pin "2") (pinfunction "K_2") (pintype "passive"))
      (node (ref "D72") (pin "2") (pinfunction "K_2") (pintype "passive"))
      (node (ref "D73") (pin "2") (pinfunction "K_2") (pintype "passive"))
      (node (ref "D74") (pin "2") (pinfunction "K_2") (pintype "passive"))
      (node (ref "D75") (pin "2") (pinfunction "K_2") (pintype "passive"))
      (node (ref "D76") (pin "2") (pinfunction "K_2") (pintype "passive"))
      (node (ref "D77") (pin "2") (pinfunction "K_2") (pintype "passive"))
      (node (ref "D78") (pin "2") (pinfunction "K_2") (pintype "passive"))
      (node (ref "D79") (pin "2") (pinfunction "K_2") (pintype "passive"))
      (node (ref "D80") (pin "2") (pinfunction "K_2") (pintype "passive"))
      (node (ref "Driver2") (pin "10") (pinfunction "B5_10") (pintype "passive"))
    )
    (net (code "30") (name "Net-(D81-K)") (class "Default")
      (node (ref "D81") (pin "2") (pinfunction "K_2") (pintype "passive"))
      (node (ref "D82") (pin "2") (pinfunction "K_2") (pintype "passive"))
      (node (ref "D83") (pin "2") (pinfunction "K_2") (pintype "passive"))
      (node (ref "D84") (pin "2") (pinfunction "K_2") (pintype "passive"))
      (node (ref "D85") (pin "2") (pinfunction "K_2") (pintype "passive"))
      (node (ref "D86") (pin "2") (pinfunction "K_2") (pintype "passive"))
      (node (ref "D87") (pin "2") (pinfunction "K_2") (pintype "passive"))
      (node (ref "D88") (pin "2") (pinfunction "K_2") (pintype "passive"))
      (node (ref "D89") (pin "2") (pinfunction "K_2") (pintype "passive"))
      (node (ref "D90") (pin "2") (pinfunction "K_2") (pintype "passive"))
      (node (ref "D91") (pin "2") (pinfunction "K_2") (pintype "passive"))
      (node (ref "D92") (pin "2") (pinfunction "K_2") (pintype "passive"))
      (node (ref "D93") (pin "2") (pinfunction "K_2") (pintype "passive"))
      (node (ref "D94") (pin "2") (pinfunction "K_2") (pintype "passive"))
      (node (ref "D95") (pin "2") (pinfunction "K_2") (pintype "passive"))
      (node (ref "D96") (pin "2") (pinfunction "K_2") (pintype "passive"))
      (node (ref "Driver2") (pin "11") (pinfunction "B4_11") (pintype "passive"))
    )
    (net (code "31") (name "Net-(D100-A)") (class "Default")
      (node (ref "D100") (pin "1") (pinfunction "A_1") (pintype "passive"))
      (node (ref "D116") (pin "1") (pinfunction "A_1") (pintype "passive"))
      (node (ref "D132") (pin "1") (pinfunction "A_1") (pintype "passive"))
      (node (ref "D148") (pin "1") (pinfunction "A_1") (pintype "passive"))
      (node (ref "D164") (pin "1") (pinfunction "A_1") (pintype "passive"))
      (node (ref "D180") (pin "1") (pinfunction "A_1") (pintype "passive"))
      (node (ref "D196") (pin "1") (pinfunction "A_1") (pintype "passive"))
      (node (ref "D20") (pin "1") (pinfunction "A_1") (pintype "passive"))
      (node (ref "D212") (pin "1") (pinfunction "A_1") (pintype "passive"))
      (node (ref "D228") (pin "1") (pinfunction "A_1") (pintype "passive"))
      (node (ref "D244") (pin "1") (pinfunction "A_1") (pintype "passive"))
      (node (ref "D36") (pin "1") (pinfunction "A_1") (pintype "passive"))
      (node (ref "D4") (pin "1") (pinfunction "A_1") (pintype "passive"))
      (node (ref "D52") (pin "1") (pinfunction "A_1") (pintype "passive"))
      (node (ref "D68") (pin "1") (pinfunction "A_1") (pintype "passive"))
      (node (ref "D84") (pin "1") (pinfunction "A_1") (pintype "passive"))
      (node (ref "R4") (pin "1") (pinfunction "1_1") (pintype "passive"))
    )
    (net (code "32") (name "Net-(D100-K)") (class "Default")
      (node (ref "D100") (pin "2") (pinfunction "K_2") (pintype "passive"))
      (node (ref "D101") (pin "2") (pinfunction "K_2") (pintype "passive"))
      (node (ref "D102") (pin "2") (pinfunction "K_2") (pintype "passive"))
      (node (ref "D103") (pin "2") (pinfunction "K_2") (pintype "passive"))
      (node (ref "D104") (pin "2") (pinfunction "K_2") (pintype "passive"))
      (node (ref "D105") (pin "2") (pinfunction "K_2") (pintype "passive"))
      (node (ref "D106") (pin "2") (pinfunction "K_2") (pintype "passive"))
      (node (ref "D107") (pin "2") (pinfunction "K_2") (pintype "passive"))
      (node (ref "D108") (pin "2") (pinfunction "K_2") (pintype "passive"))
      (node (ref "D109") (pin "2") (pinfunction "K_2") (pintype "passive"))
      (node (ref "D110") (pin "2") (pinfunction "K_2") (pintype "passive"))
      (node (ref "D111") (pin "2") (pinfunction "K_2") (pintype "passive"))
      (node (ref "D112") (pin "2") (pinfunction "K_2") (pintype "passive"))
      (node (ref "D97") (pin "2") (pinfunction "K_2") (pintype "passive"))
      (node (ref "D98") (pin "2") (pinfunction "K_2") (pintype "passive"))
      (node (ref "D99") (pin "2") (pinfunction "K_2") (pintype "passive"))
      (node (ref "Driver2") (pin "12") (pinfunction "B3_12") (pintype "passive"))
    )
    (net (code "33") (name "Net-(D101-A)") (class "Default")
      (node (ref "5") (pin "1") (pinfunction "1_1") (pintype "passive"))
      (node (ref "D101") (pin "1") (pinfunction "A_1") (pintype "passive"))
      (node (ref "D117") (pin "1") (pinfunction "A_1") (pintype "passive"))
      (node (ref "D133") (pin "1") (pinfunction "A_1") (pintype "passive"))
      (node (ref "D149") (pin "1") (pinfunction "A_1") (pintype "passive"))
      (node (ref "D165") (pin "1") (pinfunction "A_1") (pintype "passive"))
      (node (ref "D181") (pin "1") (pinfunction "A_1") (pintype "passive"))
      (node (ref "D197") (pin "1") (pinfunction "A_1") (pintype "passive"))
      (node (ref "D21") (pin "1") (pinfunction "A_1") (pintype "passive"))
      (node (ref "D213") (pin "1") (pinfunction "A_1") (pintype "passive"))
      (node (ref "D229") (pin "1") (pinfunction "A_1") (pintype "passive"))
      (node (ref "D245") (pin "1") (pinfunction "A_1") (pintype "passive"))
      (node (ref "D37") (pin "1") (pinfunction "A_1") (pintype "passive"))
      (node (ref "D5") (pin "1") (pinfunction "A_1") (pintype "passive"))
      (node (ref "D53") (pin "1") (pinfunction "A_1") (pintype "passive"))
      (node (ref "D69") (pin "1") (pinfunction "A_1") (pintype "passive"))
      (node (ref "D85") (pin "1") (pinfunction "A_1") (pintype "passive"))
    )
    (net (code "34") (name "Net-(D102-A)") (class "Default")
      (node (ref "6") (pin "1") (pinfunction "1_1") (pintype "passive"))
      (node (ref "D102") (pin "1") (pinfunction "A_1") (pintype "passive"))
      (node (ref "D118") (pin "1") (pinfunction "A_1") (pintype "passive"))
      (node (ref "D134") (pin "1") (pinfunction "A_1") (pintype "passive"))
      (node (ref "D150") (pin "1") (pinfunction "A_1") (pintype "passive"))
      (node (ref "D166") (pin "1") (pinfunction "A_1") (pintype "passive"))
      (node (ref "D182") (pin "1") (pinfunction "A_1") (pintype "passive"))
      (node (ref "D198") (pin "1") (pinfunction "A_1") (pintype "passive"))
      (node (ref "D214") (pin "1") (pinfunction "A_1") (pintype "passive"))
      (node (ref "D22") (pin "1") (pinfunction "A_1") (pintype "passive"))
      (node (ref "D230") (pin "1") (pinfunction "A_1") (pintype "passive"))
      (node (ref "D246") (pin "1") (pinfunction "A_1") (pintype "passive"))
      (node (ref "D38") (pin "1") (pinfunction "A_1") (pintype "passive"))
      (node (ref "D54") (pin "1") (pinfunction "A_1") (pintype "passive"))
      (node (ref "D6") (pin "1") (pinfunction "A_1") (pintype "passive"))
      (node (ref "D70") (pin "1") (pinfunction "A_1") (pintype "passive"))
      (node (ref "D86") (pin "1") (pinfunction "A_1") (pintype "passive"))
    )
    (net (code "35") (name "Net-(D103-A)") (class "Default")
      (node (ref "7") (pin "1") (pinfunction "1_1") (pintype "passive"))
      (node (ref "D103") (pin "1") (pinfunction "A_1") (pintype "passive"))
      (node (ref "D119") (pin "1") (pinfunction "A_1") (pintype "passive"))
      (node (ref "D135") (pin "1") (pinfunction "A_1") (pintype "passive"))
      (node (ref "D151") (pin "1") (pinfunction "A_1") (pintype "passive"))
      (node (ref "D167") (pin "1") (pinfunction "A_1") (pintype "passive"))
      (node (ref "D183") (pin "1") (pinfunction "A_1") (pintype "passive"))
      (node (ref "D199") (pin "1") (pinfunction "A_1") (pintype "passive"))
      (node (ref "D215") (pin "1") (pinfunction "A_1") (pintype "passive"))
      (node (ref "D23") (pin "1") (pinfunction "A_1") (pintype "passive"))
      (node (ref "D231") (pin "1") (pinfunction "A_1") (pintype "passive"))
      (node (ref "D247") (pin "1") (pinfunction "A_1") (pintype "passive"))
      (node (ref "D39") (pin "1") (pinfunction "A_1") (pintype "passive"))
      (node (ref "D55") (pin "1") (pinfunction "A_1") (pintype "passive"))
      (node (ref "D7") (pin "1") (pinfunction "A_1") (pintype "passive"))
      (node (ref "D71") (pin "1") (pinfunction "A_1") (pintype "passive"))
      (node (ref "D87") (pin "1") (pinfunction "A_1") (pintype "passive"))
    )
    (net (code "36") (name "Net-(D104-A)") (class "Default")
      (node (ref "8") (pin "1") (pinfunction "1_1") (pintype "passive"))
      (node (ref "D104") (pin "1") (pinfunction "A_1") (pintype "passive"))
      (node (ref "D120") (pin "1") (pinfunction "A_1") (pintype "passive"))
      (node (ref "D136") (pin "1") (pinfunction "A_1") (pintype "passive"))
      (node (ref "D152") (pin "1") (pinfunction "A_1") (pintype "passive"))
      (node (ref "D168") (pin "1") (pinfunction "A_1") (pintype "passive"))
      (node (ref "D184") (pin "1") (pinfunction "A_1") (pintype "passive"))
      (node (ref "D200") (pin "1") (pinfunction "A_1") (pintype "passive"))
      (node (ref "D216") (pin "1") (pinfunction "A_1") (pintype "passive"))
      (node (ref "D232") (pin "1") (pinfunction "A_1") (pintype "passive"))
      (node (ref "D24") (pin "1") (pinfunction "A_1") (pintype "passive"))
      (node (ref "D248") (pin "1") (pinfunction "A_1") (pintype "passive"))
      (node (ref "D40") (pin "1") (pinfunction "A_1") (pintype "passive"))
      (node (ref "D56") (pin "1") (pinfunction "A_1") (pintype "passive"))
      (node (ref "D72") (pin "1") (pinfunction "A_1") (pintype "passive"))
      (node (ref "D8") (pin "1") (pinfunction "A_1") (pintype "passive"))
      (node (ref "D88") (pin "1") (pinfunction "A_1") (pintype "passive"))
    )
    (net (code "37") (name "Net-(D105-A)") (class "Default")
      (node (ref "9") (pin "1") (pinfunction "1_1") (pintype "passive"))
      (node (ref "D105") (pin "1") (pinfunction "A_1") (pintype "passive"))
      (node (ref "D121") (pin "1") (pinfunction "A_1") (pintype "passive"))
      (node (ref "D137") (pin "1") (pinfunction "A_1") (pintype "passive"))
      (node (ref "D153") (pin "1") (pinfunction "A_1") (pintype "passive"))
      (node (ref "D169") (pin "1") (pinfunction "A_1") (pintype "passive"))
      (node (ref "D185") (pin "1") (pinfunction "A_1") (pintype "passive"))
      (node (ref "D201") (pin "1") (pinfunction "A_1") (pintype "passive"))
      (node (ref "D217") (pin "1") (pinfunction "A_1") (pintype "passive"))
      (node (ref "D233") (pin "1") (pinfunction "A_1") (pintype "passive"))
      (node (ref "D249") (pin "1") (pinfunction "A_1") (pintype "passive"))
      (node (ref "D25") (pin "1") (pinfunction "A_1") (pintype "passive"))
      (node (ref "D41") (pin "1") (pinfunction "A_1") (pintype "passive"))
      (node (ref "D57") (pin "1") (pinfunction "A_1") (pintype "passive"))
      (node (ref "D73") (pin "1") (pinfunction "A_1") (pintype "passive"))
      (node (ref "D89") (pin "1") (pinfunction "A_1") (pintype "passive"))
      (node (ref "D9") (pin "1") (pinfunction "A_1") (pintype "passive"))
    )
    (net (code "38") (name "Net-(D107-A)") (class "Default")
      (node (ref "11") (pin "1") (pinfunction "1_1") (pintype "passive"))
      (node (ref "D107") (pin "1") (pinfunction "A_1") (pintype "passive"))
      (node (ref "D11") (pin "1") (pinfunction "A_1") (pintype "passive"))
      (node (ref "D123") (pin "1") (pinfunction "A_1") (pintype "passive"))
      (node (ref "D139") (pin "1") (pinfunction "A_1") (pintype "passive"))
      (node (ref "D155") (pin "1") (pinfunction "A_1") (pintype "passive"))
      (node (ref "D171") (pin "1") (pinfunction "A_1") (pintype "passive"))
      (node (ref "D187") (pin "1") (pinfunction "A_1") (pintype "passive"))
      (node (ref "D203") (pin "1") (pinfunction "A_1") (pintype "passive"))
      (node (ref "D219") (pin "1") (pinfunction "A_1") (pintype "passive"))
      (node (ref "D235") (pin "1") (pinfunction "A_1") (pintype "passive"))
      (node (ref "D251") (pin "1") (pinfunction "A_1") (pintype "passive"))
      (node (ref "D27") (pin "1") (pinfunction "A_1") (pintype "passive"))
      (node (ref "D43") (pin "1") (pinfunction "A_1") (pintype "passive"))
      (node (ref "D59") (pin "1") (pinfunction "A_1") (pintype "passive"))
      (node (ref "D75") (pin "1") (pinfunction "A_1") (pintype "passive"))
      (node (ref "D91") (pin "1") (pinfunction "A_1") (pintype "passive"))
    )
    (net (code "39") (name "Net-(D108-A)") (class "Default")
      (node (ref "12") (pin "1") (pinfunction "1_1") (pintype "passive"))
      (node (ref "D108") (pin "1") (pinfunction "A_1") (pintype "passive"))
      (node (ref "D12") (pin "1") (pinfunction "A_1") (pintype "passive"))
      (node (ref "D124") (pin "1") (pinfunction "A_1") (pintype "passive"))
      (node (ref "D140") (pin "1") (pinfunction "A_1") (pintype "passive"))
      (node (ref "D156") (pin "1") (pinfunction "A_1") (pintype "passive"))
      (node (ref "D172") (pin "1") (pinfunction "A_1") (pintype "passive"))
      (node (ref "D188") (pin "1") (pinfunction "A_1") (pintype "passive"))
      (node (ref "D204") (pin "1") (pinfunction "A_1") (pintype "passive"))
      (node (ref "D220") (pin "1") (pinfunction "A_1") (pintype "passive"))
      (node (ref "D236") (pin "1") (pinfunction "A_1") (pintype "passive"))
      (node (ref "D252") (pin "1") (pinfunction "A_1") (pintype "passive"))
      (node (ref "D28") (pin "1") (pinfunction "A_1") (pintype "passive"))
      (node (ref "D44") (pin "1") (pinfunction "A_1") (pintype "passive"))
      (node (ref "D60") (pin "1") (pinfunction "A_1") (pintype "passive"))
      (node (ref "D76") (pin "1") (pinfunction "A_1") (pintype "passive"))
      (node (ref "D92") (pin "1") (pinfunction "A_1") (pintype "passive"))
    )
    (net (code "40") (name "Net-(D109-A)") (class "Default")
      (node (ref "13") (pin "1") (pinfunction "1_1") (pintype "passive"))
      (node (ref "D109") (pin "1") (pinfunction "A_1") (pintype "passive"))
      (node (ref "D125") (pin "1") (pinfunction "A_1") (pintype "passive"))
      (node (ref "D13") (pin "1") (pinfunction "A_1") (pintype "passive"))
      (node (ref "D141") (pin "1") (pinfunction "A_1") (pintype "passive"))
      (node (ref "D157") (pin "1") (pinfunction "A_1") (pintype "passive"))
      (node (ref "D173") (pin "1") (pinfunction "A_1") (pintype "passive"))
      (node (ref "D189") (pin "1") (pinfunction "A_1") (pintype "passive"))
      (node (ref "D205") (pin "1") (pinfunction "A_1") (pintype "passive"))
      (node (ref "D221") (pin "1") (pinfunction "A_1") (pintype "passive"))
      (node (ref "D237") (pin "1") (pinfunction "A_1") (pintype "passive"))
      (node (ref "D253") (pin "1") (pinfunction "A_1") (pintype "passive"))
      (node (ref "D29") (pin "1") (pinfunction "A_1") (pintype "passive"))
      (node (ref "D45") (pin "1") (pinfunction "A_1") (pintype "passive"))
      (node (ref "D61") (pin "1") (pinfunction "A_1") (pintype "passive"))
      (node (ref "D77") (pin "1") (pinfunction "A_1") (pintype "passive"))
      (node (ref "D93") (pin "1") (pinfunction "A_1") (pintype "passive"))
    )
    (net (code "41") (name "Net-(D110-A)") (class "Default")
      (node (ref "14") (pin "1") (pinfunction "1_1") (pintype "passive"))
      (node (ref "D110") (pin "1") (pinfunction "A_1") (pintype "passive"))
      (node (ref "D126") (pin "1") (pinfunction "A_1") (pintype "passive"))
      (node (ref "D14") (pin "1") (pinfunction "A_1") (pintype "passive"))
      (node (ref "D142") (pin "1") (pinfunction "A_1") (pintype "passive"))
      (node (ref "D158") (pin "1") (pinfunction "A_1") (pintype "passive"))
      (node (ref "D174") (pin "1") (pinfunction "A_1") (pintype "passive"))
      (node (ref "D190") (pin "1") (pinfunction "A_1") (pintype "passive"))
      (node (ref "D206") (pin "1") (pinfunction "A_1") (pintype "passive"))
      (node (ref "D222") (pin "1") (pinfunction "A_1") (pintype "passive"))
      (node (ref "D238") (pin "1") (pinfunction "A_1") (pintype "passive"))
      (node (ref "D254") (pin "1") (pinfunction "A_1") (pintype "passive"))
      (node (ref "D30") (pin "1") (pinfunction "A_1") (pintype "passive"))
      (node (ref "D46") (pin "1") (pinfunction "A_1") (pintype "passive"))
      (node (ref "D62") (pin "1") (pinfunction "A_1") (pintype "passive"))
      (node (ref "D78") (pin "1") (pinfunction "A_1") (pintype "passive"))
      (node (ref "D94") (pin "1") (pinfunction "A_1") (pintype "passive"))
    )
    (net (code "42") (name "Net-(D111-A)") (class "Default")
      (node (ref "15") (pin "1") (pinfunction "1_1") (pintype "passive"))
      (node (ref "D111") (pin "1") (pinfunction "A_1") (pintype "passive"))
      (node (ref "D127") (pin "1") (pinfunction "A_1") (pintype "passive"))
      (node (ref "D143") (pin "1") (pinfunction "A_1") (pintype "passive"))
      (node (ref "D15") (pin "1") (pinfunction "A_1") (pintype "passive"))
      (node (ref "D159") (pin "1") (pinfunction "A_1") (pintype "passive"))
      (node (ref "D175") (pin "1") (pinfunction "A_1") (pintype "passive"))
      (node (ref "D191") (pin "1") (pinfunction "A_1") (pintype "passive"))
      (node (ref "D207") (pin "1") (pinfunction "A_1") (pintype "passive"))
      (node (ref "D223") (pin "1") (pinfunction "A_1") (pintype "passive"))
      (node (ref "D239") (pin "1") (pinfunction "A_1") (pintype "passive"))
      (node (ref "D255") (pin "1") (pinfunction "A_1") (pintype "passive"))
      (node (ref "D31") (pin "1") (pinfunction "A_1") (pintype "passive"))
      (node (ref "D47") (pin "1") (pinfunction "A_1") (pintype "passive"))
      (node (ref "D63") (pin "1") (pinfunction "A_1") (pintype "passive"))
      (node (ref "D79") (pin "1") (pinfunction "A_1") (pintype "passive"))
      (node (ref "D95") (pin "1") (pinfunction "A_1") (pintype "passive"))
    )
    (net (code "43") (name "Net-(D112-A)") (class "Default")
      (node (ref "16") (pin "1") (pinfunction "1_1") (pintype "passive"))
      (node (ref "D112") (pin "1") (pinfunction "A_1") (pintype "passive"))
      (node (ref "D128") (pin "1") (pinfunction "A_1") (pintype "passive"))
      (node (ref "D144") (pin "1") (pinfunction "A_1") (pintype "passive"))
      (node (ref "D16") (pin "1") (pinfunction "A_1") (pintype "passive"))
      (node (ref "D160") (pin "1") (pinfunction "A_1") (pintype "passive"))
      (node (ref "D176") (pin "1") (pinfunction "A_1") (pintype "passive"))
      (node (ref "D192") (pin "1") (pinfunction "A_1") (pintype "passive"))
      (node (ref "D208") (pin "1") (pinfunction "A_1") (pintype "passive"))
      (node (ref "D224") (pin "1") (pinfunction "A_1") (pintype "passive"))
      (node (ref "D240") (pin "1") (pinfunction "A_1") (pintype "passive"))
      (node (ref "D256") (pin "1") (pinfunction "A_1") (pintype "passive"))
      (node (ref "D32") (pin "1") (pinfunction "A_1") (pintype "passive"))
      (node (ref "D48") (pin "1") (pinfunction "A_1") (pintype "passive"))
      (node (ref "D64") (pin "1") (pinfunction "A_1") (pintype "passive"))
      (node (ref "D80") (pin "1") (pinfunction "A_1") (pintype "passive"))
      (node (ref "D96") (pin "1") (pinfunction "A_1") (pintype "passive"))
    )
    (net (code "44") (name "Net-(D113-K)") (class "Default")
      (node (ref "D113") (pin "2") (pinfunction "K_2") (pintype "passive"))
      (node (ref "D114") (pin "2") (pinfunction "K_2") (pintype "passive"))
      (node (ref "D115") (pin "2") (pinfunction "K_2") (pintype "passive"))
      (node (ref "D116") (pin "2") (pinfunction "K_2") (pintype "passive"))
      (node (ref "D117") (pin "2") (pinfunction "K_2") (pintype "passive"))
      (node (ref "D118") (pin "2") (pinfunction "K_2") (pintype "passive"))
      (node (ref "D119") (pin "2") (pinfunction "K_2") (pintype "passive"))
      (node (ref "D120") (pin "2") (pinfunction "K_2") (pintype "passive"))
      (node (ref "D121") (pin "2") (pinfunction "K_2") (pintype "passive"))
      (node (ref "D122") (pin "2") (pinfunction "K_2") (pintype "passive"))
      (node (ref "D123") (pin "2") (pinfunction "K_2") (pintype "passive"))
      (node (ref "D124") (pin "2") (pinfunction "K_2") (pintype "passive"))
      (node (ref "D125") (pin "2") (pinfunction "K_2") (pintype "passive"))
      (node (ref "D126") (pin "2") (pinfunction "K_2") (pintype "passive"))
      (node (ref "D127") (pin "2") (pinfunction "K_2") (pintype "passive"))
      (node (ref "D128") (pin "2") (pinfunction "K_2") (pintype "passive"))
      (node (ref "Driver2") (pin "13") (pinfunction "B2_13") (pintype "passive"))
    )
    (net (code "45") (name "Net-(D114-A)") (class "Default")
      (node (ref "D114") (pin "1") (pinfunction "A_1") (pintype "passive"))
      (node (ref "D130") (pin "1") (pinfunction "A_1") (pintype "passive"))
      (node (ref "D146") (pin "1") (pinfunction "A_1") (pintype "passive"))
      (node (ref "D162") (pin "1") (pinfunction "A_1") (pintype "passive"))
      (node (ref "D178") (pin "1") (pinfunction "A_1") (pintype "passive"))
      (node (ref "D18") (pin "1") (pinfunction "A_1") (pintype "passive"))
      (node (ref "D194") (pin "1") (pinfunction "A_1") (pintype "passive"))
      (node (ref "D2") (pin "1") (pinfunction "A_1") (pintype "passive"))
      (node (ref "D210") (pin "1") (pinfunction "A_1") (pintype "passive"))
      (node (ref "D226") (pin "1") (pinfunction "A_1") (pintype "passive"))
      (node (ref "D242") (pin "1") (pinfunction "A_1") (pintype "passive"))
      (node (ref "D34") (pin "1") (pinfunction "A_1") (pintype "passive"))
      (node (ref "D50") (pin "1") (pinfunction "A_1") (pintype "passive"))
      (node (ref "D66") (pin "1") (pinfunction "A_1") (pintype "passive"))
      (node (ref "D82") (pin "1") (pinfunction "A_1") (pintype "passive"))
      (node (ref "D98") (pin "1") (pinfunction "A_1") (pintype "passive"))
      (node (ref "R2") (pin "1") (pinfunction "1_1") (pintype "passive"))
    )
    (net (code "46") (name "Net-(D115-A)") (class "Default")
      (node (ref "D115") (pin "1") (pinfunction "A_1") (pintype "passive"))
      (node (ref "D131") (pin "1") (pinfunction "A_1") (pintype "passive"))
      (node (ref "D147") (pin "1") (pinfunction "A_1") (pintype "passive"))
      (node (ref "D163") (pin "1") (pinfunction "A_1") (pintype "passive"))
      (node (ref "D179") (pin "1") (pinfunction "A_1") (pintype "passive"))
      (node (ref "D19") (pin "1") (pinfunction "A_1") (pintype "passive"))
      (node (ref "D195") (pin "1") (pinfunction "A_1") (pintype "passive"))
      (node (ref "D211") (pin "1") (pinfunction "A_1") (pintype "passive"))
      (node (ref "D227") (pin "1") (pinfunction "A_1") (pintype "passive"))
      (node (ref "D243") (pin "1") (pinfunction "A_1") (pintype "passive"))
      (node (ref "D3") (pin "1") (pinfunction "A_1") (pintype "passive"))
      (node (ref "D35") (pin "1") (pinfunction "A_1") (pintype "passive"))
      (node (ref "D51") (pin "1") (pinfunction "A_1") (pintype "passive"))
      (node (ref "D67") (pin "1") (pinfunction "A_1") (pintype "passive"))
      (node (ref "D83") (pin "1") (pinfunction "A_1") (pintype "passive"))
      (node (ref "D99") (pin "1") (pinfunction "A_1") (pintype "passive"))
      (node (ref "R3") (pin "1") (pinfunction "1_1") (pintype "passive"))
    )
    (net (code "47") (name "Net-(D129-K)") (class "Default")
      (node (ref "D129") (pin "2") (pinfunction "K_2") (pintype "passive"))
      (node (ref "D130") (pin "2") (pinfunction "K_2") (pintype "passive"))
      (node (ref "D131") (pin "2") (pinfunction "K_2") (pintype "passive"))
      (node (ref "D132") (pin "2") (pinfunction "K_2") (pintype "passive"))
      (node (ref "D133") (pin "2") (pinfunction "K_2") (pintype "passive"))
      (node (ref "D134") (pin "2") (pinfunction "K_2") (pintype "passive"))
      (node (ref "D135") (pin "2") (pinfunction "K_2") (pintype "passive"))
      (node (ref "D136") (pin "2") (pinfunction "K_2") (pintype "passive"))
      (node (ref "D137") (pin "2") (pinfunction "K_2") (pintype "passive"))
      (node (ref "D138") (pin "2") (pinfunction "K_2") (pintype "passive"))
      (node (ref "D139") (pin "2") (pinfunction "K_2") (pintype "passive"))
      (node (ref "D140") (pin "2") (pinfunction "K_2") (pintype "passive"))
      (node (ref "D141") (pin "2") (pinfunction "K_2") (pintype "passive"))
      (node (ref "D142") (pin "2") (pinfunction "K_2") (pintype "passive"))
      (node (ref "D143") (pin "2") (pinfunction "K_2") (pintype "passive"))
      (node (ref "D144") (pin "2") (pinfunction "K_2") (pintype "passive"))
      (node (ref "Driver3") (pin "10") (pinfunction "B5_10") (pintype "passive"))
    )
    (net (code "48") (name "Net-(D145-K)") (class "Default")
      (node (ref "D145") (pin "2") (pinfunction "K_2") (pintype "passive"))
      (node (ref "D146") (pin "2") (pinfunction "K_2") (pintype "passive"))
      (node (ref "D147") (pin "2") (pinfunction "K_2") (pintype "passive"))
      (node (ref "D148") (pin "2") (pinfunction "K_2") (pintype "passive"))
      (node (ref "D149") (pin "2") (pinfunction "K_2") (pintype "passive"))
      (node (ref "D150") (pin "2") (pinfunction "K_2") (pintype "passive"))
      (node (ref "D151") (pin "2") (pinfunction "K_2") (pintype "passive"))
      (node (ref "D152") (pin "2") (pinfunction "K_2") (pintype "passive"))
      (node (ref "D153") (pin "2") (pinfunction "K_2") (pintype "passive"))
      (node (ref "D154") (pin "2") (pinfunction "K_2") (pintype "passive"))
      (node (ref "D155") (pin "2") (pinfunction "K_2") (pintype "passive"))
      (node (ref "D156") (pin "2") (pinfunction "K_2") (pintype "passive"))
      (node (ref "D157") (pin "2") (pinfunction "K_2") (pintype "passive"))
      (node (ref "D158") (pin "2") (pinfunction "K_2") (pintype "passive"))
      (node (ref "D159") (pin "2") (pinfunction "K_2") (pintype "passive"))
      (node (ref "D160") (pin "2") (pinfunction "K_2") (pintype "passive"))
      (node (ref "Driver3") (pin "11") (pinfunction "B4_11") (pintype "passive"))
    )
    (net (code "49") (name "Net-(D161-K)") (class "Default")
      (node (ref "D161") (pin "2") (pinfunction "K_2") (pintype "passive"))
      (node (ref "D162") (pin "2") (pinfunction "K_2") (pintype "passive"))
      (node (ref "D163") (pin "2") (pinfunction "K_2") (pintype "passive"))
      (node (ref "D164") (pin "2") (pinfunction "K_2") (pintype "passive"))
      (node (ref "D165") (pin "2") (pinfunction "K_2") (pintype "passive"))
      (node (ref "D166") (pin "2") (pinfunction "K_2") (pintype "passive"))
      (node (ref "D167") (pin "2") (pinfunction "K_2") (pintype "passive"))
      (node (ref "D168") (pin "2") (pinfunction "K_2") (pintype "passive"))
      (node (ref "D169") (pin "2") (pinfunction "K_2") (pintype "passive"))
      (node (ref "D170") (pin "2") (pinfunction "K_2") (pintype "passive"))
      (node (ref "D171") (pin "2") (pinfunction "K_2") (pintype "passive"))
      (node (ref "D172") (pin "2") (pinfunction "K_2") (pintype "passive"))
      (node (ref "D173") (pin "2") (pinfunction "K_2") (pintype "passive"))
      (node (ref "D174") (pin "2") (pinfunction "K_2") (pintype "passive"))
      (node (ref "D175") (pin "2") (pinfunction "K_2") (pintype "passive"))
      (node (ref "D176") (pin "2") (pinfunction "K_2") (pintype "passive"))
      (node (ref "Driver3") (pin "12") (pinfunction "B3_12") (pintype "passive"))
    )
    (net (code "50") (name "Net-(D177-K)") (class "Default")
      (node (ref "D177") (pin "2") (pinfunction "K_2") (pintype "passive"))
      (node (ref "D178") (pin "2") (pinfunction "K_2") (pintype "passive"))
      (node (ref "D179") (pin "2") (pinfunction "K_2") (pintype "passive"))
      (node (ref "D180") (pin "2") (pinfunction "K_2") (pintype "passive"))
      (node (ref "D181") (pin "2") (pinfunction "K_2") (pintype "passive"))
      (node (ref "D182") (pin "2") (pinfunction "K_2") (pintype "passive"))
      (node (ref "D183") (pin "2") (pinfunction "K_2") (pintype "passive"))
      (node (ref "D184") (pin "2") (pinfunction "K_2") (pintype "passive"))
      (node (ref "D185") (pin "2") (pinfunction "K_2") (pintype "passive"))
      (node (ref "D186") (pin "2") (pinfunction "K_2") (pintype "passive"))
      (node (ref "D187") (pin "2") (pinfunction "K_2") (pintype "passive"))
      (node (ref "D188") (pin "2") (pinfunction "K_2") (pintype "passive"))
      (node (ref "D189") (pin "2") (pinfunction "K_2") (pintype "passive"))
      (node (ref "D190") (pin "2") (pinfunction "K_2") (pintype "passive"))
      (node (ref "D191") (pin "2") (pinfunction "K_2") (pintype "passive"))
      (node (ref "D192") (pin "2") (pinfunction "K_2") (pintype "passive"))
      (node (ref "Driver3") (pin "13") (pinfunction "B2_13") (pintype "passive"))
    )
    (net (code "51") (name "Net-(D193-K)") (class "Default")
      (node (ref "D193") (pin "2") (pinfunction "K_2") (pintype "passive"))
      (node (ref "D194") (pin "2") (pinfunction "K_2") (pintype "passive"))
      (node (ref "D195") (pin "2") (pinfunction "K_2") (pintype "passive"))
      (node (ref "D196") (pin "2") (pinfunction "K_2") (pintype "passive"))
      (node (ref "D197") (pin "2") (pinfunction "K_2") (pintype "passive"))
      (node (ref "D198") (pin "2") (pinfunction "K_2") (pintype "passive"))
      (node (ref "D199") (pin "2") (pinfunction "K_2") (pintype "passive"))
      (node (ref "D200") (pin "2") (pinfunction "K_2") (pintype "passive"))
      (node (ref "D201") (pin "2") (pinfunction "K_2") (pintype "passive"))
      (node (ref "D202") (pin "2") (pinfunction "K_2") (pintype "passive"))
      (node (ref "D203") (pin "2") (pinfunction "K_2") (pintype "passive"))
      (node (ref "D204") (pin "2") (pinfunction "K_2") (pintype "passive"))
      (node (ref "D205") (pin "2") (pinfunction "K_2") (pintype "passive"))
      (node (ref "D206") (pin "2") (pinfunction "K_2") (pintype "passive"))
      (node (ref "D207") (pin "2") (pinfunction "K_2") (pintype "passive"))
      (node (ref "D208") (pin "2") (pinfunction "K_2") (pintype "passive"))
      (node (ref "Driver4") (pin "10") (pinfunction "B5_10") (pintype "passive"))
    )
    (net (code "52") (name "Net-(D209-K)") (class "Default")
      (node (ref "D209") (pin "2") (pinfunction "K_2") (pintype "passive"))
      (node (ref "D210") (pin "2") (pinfunction "K_2") (pintype "passive"))
      (node (ref "D211") (pin "2") (pinfunction "K_2") (pintype "passive"))
      (node (ref "D212") (pin "2") (pinfunction "K_2") (pintype "passive"))
      (node (ref "D213") (pin "2") (pinfunction "K_2") (pintype "passive"))
      (node (ref "D214") (pin "2") (pinfunction "K_2") (pintype "passive"))
      (node (ref "D215") (pin "2") (pinfunction "K_2") (pintype "passive"))
      (node (ref "D216") (pin "2") (pinfunction "K_2") (pintype "passive"))
      (node (ref "D217") (pin "2") (pinfunction "K_2") (pintype "passive"))
      (node (ref "D218") (pin "2") (pinfunction "K_2") (pintype "passive"))
      (node (ref "D219") (pin "2") (pinfunction "K_2") (pintype "passive"))
      (node (ref "D220") (pin "2") (pinfunction "K_2") (pintype "passive"))
      (node (ref "D221") (pin "2") (pinfunction "K_2") (pintype "passive"))
      (node (ref "D222") (pin "2") (pinfunction "K_2") (pintype "passive"))
      (node (ref "D223") (pin "2") (pinfunction "K_2") (pintype "passive"))
      (node (ref "D224") (pin "2") (pinfunction "K_2") (pintype "passive"))
      (node (ref "Driver4") (pin "11") (pinfunction "B4_11") (pintype "passive"))
    )
    (net (code "53") (name "Net-(D225-K)") (class "Default")
      (node (ref "D225") (pin "2") (pinfunction "K_2") (pintype "passive"))
      (node (ref "D226") (pin "2") (pinfunction "K_2") (pintype "passive"))
      (node (ref "D227") (pin "2") (pinfunction "K_2") (pintype "passive"))
      (node (ref "D228") (pin "2") (pinfunction "K_2") (pintype "passive"))
      (node (ref "D229") (pin "2") (pinfunction "K_2") (pintype "passive"))
      (node (ref "D230") (pin "2") (pinfunction "K_2") (pintype "passive"))
      (node (ref "D231") (pin "2") (pinfunction "K_2") (pintype "passive"))
      (node (ref "D232") (pin "2") (pinfunction "K_2") (pintype "passive"))
      (node (ref "D233") (pin "2") (pinfunction "K_2") (pintype "passive"))
      (node (ref "D234") (pin "2") (pinfunction "K_2") (pintype "passive"))
      (node (ref "D235") (pin "2") (pinfunction "K_2") (pintype "passive"))
      (node (ref "D236") (pin "2") (pinfunction "K_2") (pintype "passive"))
      (node (ref "D237") (pin "2") (pinfunction "K_2") (pintype "passive"))
      (node (ref "D238") (pin "2") (pinfunction "K_2") (pintype "passive"))
      (node (ref "D239") (pin "2") (pinfunction "K_2") (pintype "passive"))
      (node (ref "D240") (pin "2") (pinfunction "K_2") (pintype "passive"))
      (node (ref "Driver4") (pin "12") (pinfunction "B3_12") (pintype "passive"))
    )
    (net (code "54") (name "Net-(D241-K)") (class "Default")
      (node (ref "D241") (pin "2") (pinfunction "K_2") (pintype "passive"))
      (node (ref "D242") (pin "2") (pinfunction "K_2") (pintype "passive"))
      (node (ref "D243") (pin "2") (pinfunction "K_2") (pintype "passive"))
      (node (ref "D244") (pin "2") (pinfunction "K_2") (pintype "passive"))
      (node (ref "D245") (pin "2") (pinfunction "K_2") (pintype "passive"))
      (node (ref "D246") (pin "2") (pinfunction "K_2") (pintype "passive"))
      (node (ref "D247") (pin "2") (pinfunction "K_2") (pintype "passive"))
      (node (ref "D248") (pin "2") (pinfunction "K_2") (pintype "passive"))
      (node (ref "D249") (pin "2") (pinfunction "K_2") (pintype "passive"))
      (node (ref "D250") (pin "2") (pinfunction "K_2") (pintype "passive"))
      (node (ref "D251") (pin "2") (pinfunction "K_2") (pintype "passive"))
      (node (ref "D252") (pin "2") (pinfunction "K_2") (pintype "passive"))
      (node (ref "D253") (pin "2") (pinfunction "K_2") (pintype "passive"))
      (node (ref "D254") (pin "2") (pinfunction "K_2") (pintype "passive"))
      (node (ref "D255") (pin "2") (pinfunction "K_2") (pintype "passive"))
      (node (ref "D256") (pin "2") (pinfunction "K_2") (pintype "passive"))
      (node (ref "Driver4") (pin "13") (pinfunction "B2_13") (pintype "passive"))
    )
    (net (code "55") (name "Net-(Driver1-A1)") (class "Default")
      (node (ref "Driver1") (pin "1") (pinfunction "A1_1") (pintype "passive"))
      (node (ref "DémuxBas") (pin "5") (pinfunction "A5_5") (pintype "passive"))
    )
    (net (code "56") (name "Net-(Driver1-A3)") (class "Default")
      (node (ref "Driver1") (pin "3") (pinfunction "A3_3") (pintype "passive"))
      (node (ref "DémuxBas") (pin "3") (pinfunction "A3_3") (pintype "passive"))
    )
    (net (code "57") (name "Net-(Driver1-A5)") (class "Default")
      (node (ref "Driver1") (pin "5") (pinfunction "A5_5") (pintype "passive"))
      (node (ref "DémuxBas") (pin "4") (pinfunction "A4_4") (pintype "passive"))
    )
    (net (code "58") (name "Net-(Driver1-B7)") (class "Default")
      (node (ref "Driver1") (pin "8") (pinfunction "B7_8") (pintype "passive"))
      (node (ref "DémuxBas") (pin "2") (pinfunction "A2_2") (pintype "passive"))
    )
    (net (code "59") (name "Net-(Driver2-A1)") (class "Default")
      (node (ref "Driver2") (pin "1") (pinfunction "A1_1") (pintype "passive"))
      (node (ref "DémuxBas") (pin "1") (pinfunction "A1_1") (pintype "passive"))
    )
    (net (code "60") (name "Net-(Driver2-A3)") (class "Default")
      (node (ref "Driver2") (pin "3") (pinfunction "A3_3") (pintype "passive"))
      (node (ref "DémuxHaut") (pin "6") (pinfunction "A6_6") (pintype "passive"))
    )
    (net (code "61") (name "Net-(Driver2-A5)") (class "Default")
      (node (ref "Driver2") (pin "5") (pinfunction "A5_5") (pintype "passive"))
      (node (ref "DémuxHaut") (pin "5") (pinfunction "A5_5") (pintype "passive"))
    )
    (net (code "62") (name "Net-(Driver2-B7)") (class "Default")
      (node (ref "Driver2") (pin "8") (pinfunction "B7_8") (pintype "passive"))
      (node (ref "DémuxHaut") (pin "4") (pinfunction "A4_4") (pintype "passive"))
    )
    (net (code "63") (name "Net-(Driver3-A1)") (class "Default")
      (node (ref "Driver3") (pin "1") (pinfunction "A1_1") (pintype "passive"))
      (node (ref "DémuxBas") (pin "11") (pinfunction "B2_11") (pintype "passive"))
    )
    (net (code "64") (name "Net-(Driver3-A3)") (class "Default")
      (node (ref "Driver3") (pin "3") (pinfunction "A3_3") (pintype "passive"))
      (node (ref "DémuxBas") (pin "12") (pinfunction "B1_12") (pintype "passive"))
    )
    (net (code "65") (name "Net-(Driver3-A5)") (class "Default")
      (node (ref "Driver3") (pin "5") (pinfunction "A5_5") (pintype "passive"))
      (node (ref "DémuxHaut") (pin "8") (pinfunction "B5_8") (pintype "passive"))
    )
    (net (code "66") (name "Net-(Driver3-B7)") (class "Default")
      (node (ref "Driver3") (pin "8") (pinfunction "B7_8") (pintype "passive"))
      (node (ref "DémuxHaut") (pin "7") (pinfunction "B6_7") (pintype "passive"))
    )
    (net (code "67") (name "Net-(Driver4-A1)") (class "Default")
      (node (ref "Driver4") (pin "1") (pinfunction "A1_1") (pintype "passive"))
      (node (ref "DémuxBas") (pin "8") (pinfunction "B5_8") (pintype "passive"))
    )
    (net (code "68") (name "Net-(Driver4-A3)") (class "Default")
      (node (ref "Driver4") (pin "3") (pinfunction "A3_3") (pintype "passive"))
      (node (ref "DémuxBas") (pin "7") (pinfunction "B6_7") (pintype "passive"))
    )
    (net (code "69") (name "Net-(Driver4-A5)") (class "Default")
      (node (ref "Driver4") (pin "5") (pinfunction "A5_5") (pintype "passive"))
      (node (ref "DémuxBas") (pin "9") (pinfunction "B4_9") (pintype "passive"))
    )
    (net (code "70") (name "Net-(Driver4-B7)") (class "Default")
      (node (ref "Driver4") (pin "8") (pinfunction "B7_8") (pintype "passive"))
      (node (ref "DémuxBas") (pin "10") (pinfunction "B3_10") (pintype "passive"))
    )
    (net (code "71") (name "Net-(DémuxHaut-A2)") (class "Default")
      (node (ref "DémuxHaut") (pin "2") (pinfunction "A2_2") (pintype "passive"))
      (node (ref "IC*1") (pin "22") (pinfunction "RB11_22") (pintype "passive"))
    )
    (net (code "72") (name "Net-(DémuxHaut-A3)") (class "Default")
      (node (ref "DémuxHaut") (pin "3") (pinfunction "A3_3") (pintype "passive"))
      (node (ref "IC*1") (pin "23") (pinfunction "RB12_23") (pintype "passive"))
    )
    (net (code "73") (name "Net-(DémuxHaut-B3)") (class "Default")
      (node (ref "DémuxHaut") (pin "10") (pinfunction "B3_10") (pintype "passive"))
      (node (ref "IC*1") (pin "24") (pinfunction "RB13_24") (pintype "passive"))
    )
    (net (code "74") (name "Net-(DémuxHaut-B4)") (class "Default")
      (node (ref "DémuxHaut") (pin "9") (pinfunction "B4_9") (pintype "passive"))
      (node (ref "IC*1") (pin "25") (pinfunction "RB14_25") (pintype "passive"))
    )
    (net (code "75") (name "Net-(IC*1-Vcap)") (class "Default")
      (node (ref "C5") (pin "1") (pinfunction "1_1") (pintype "passive"))
      (node (ref "IC*1") (pin "20") (pinfunction "Vcap_20") (pintype "passive"))
    )
    (net (code "76") (name "unconnected-(DémuxHaut-A1-Pad1)") (class "Default")
      (node (ref "DémuxHaut") (pin "1") (pinfunction "A1_1") (pintype "passive"))
    )
    (net (code "77") (name "unconnected-(DémuxHaut-B2-Pad11)") (class "Default")
      (node (ref "DémuxHaut") (pin "11") (pinfunction "B2_11") (pintype "passive"))
    )
    (net (code "78") (name "unconnected-(IC*1-RB15-Pad26)") (class "Default")
      (node (ref "IC*1") (pin "26") (pinfunction "RB15_26") (pintype "passive"))
    )
    (net (code "79") (name "unconnected-(pickit-LVP-Pad6)") (class "Default")
      (node (ref "pickit") (pin "6") (pinfunction "LVP_6") (pintype "passive"))
    )
  )
)
